# NeuroStimDuino_v1_1.net
KiCad netlist of a schematic drawn in EAGLE
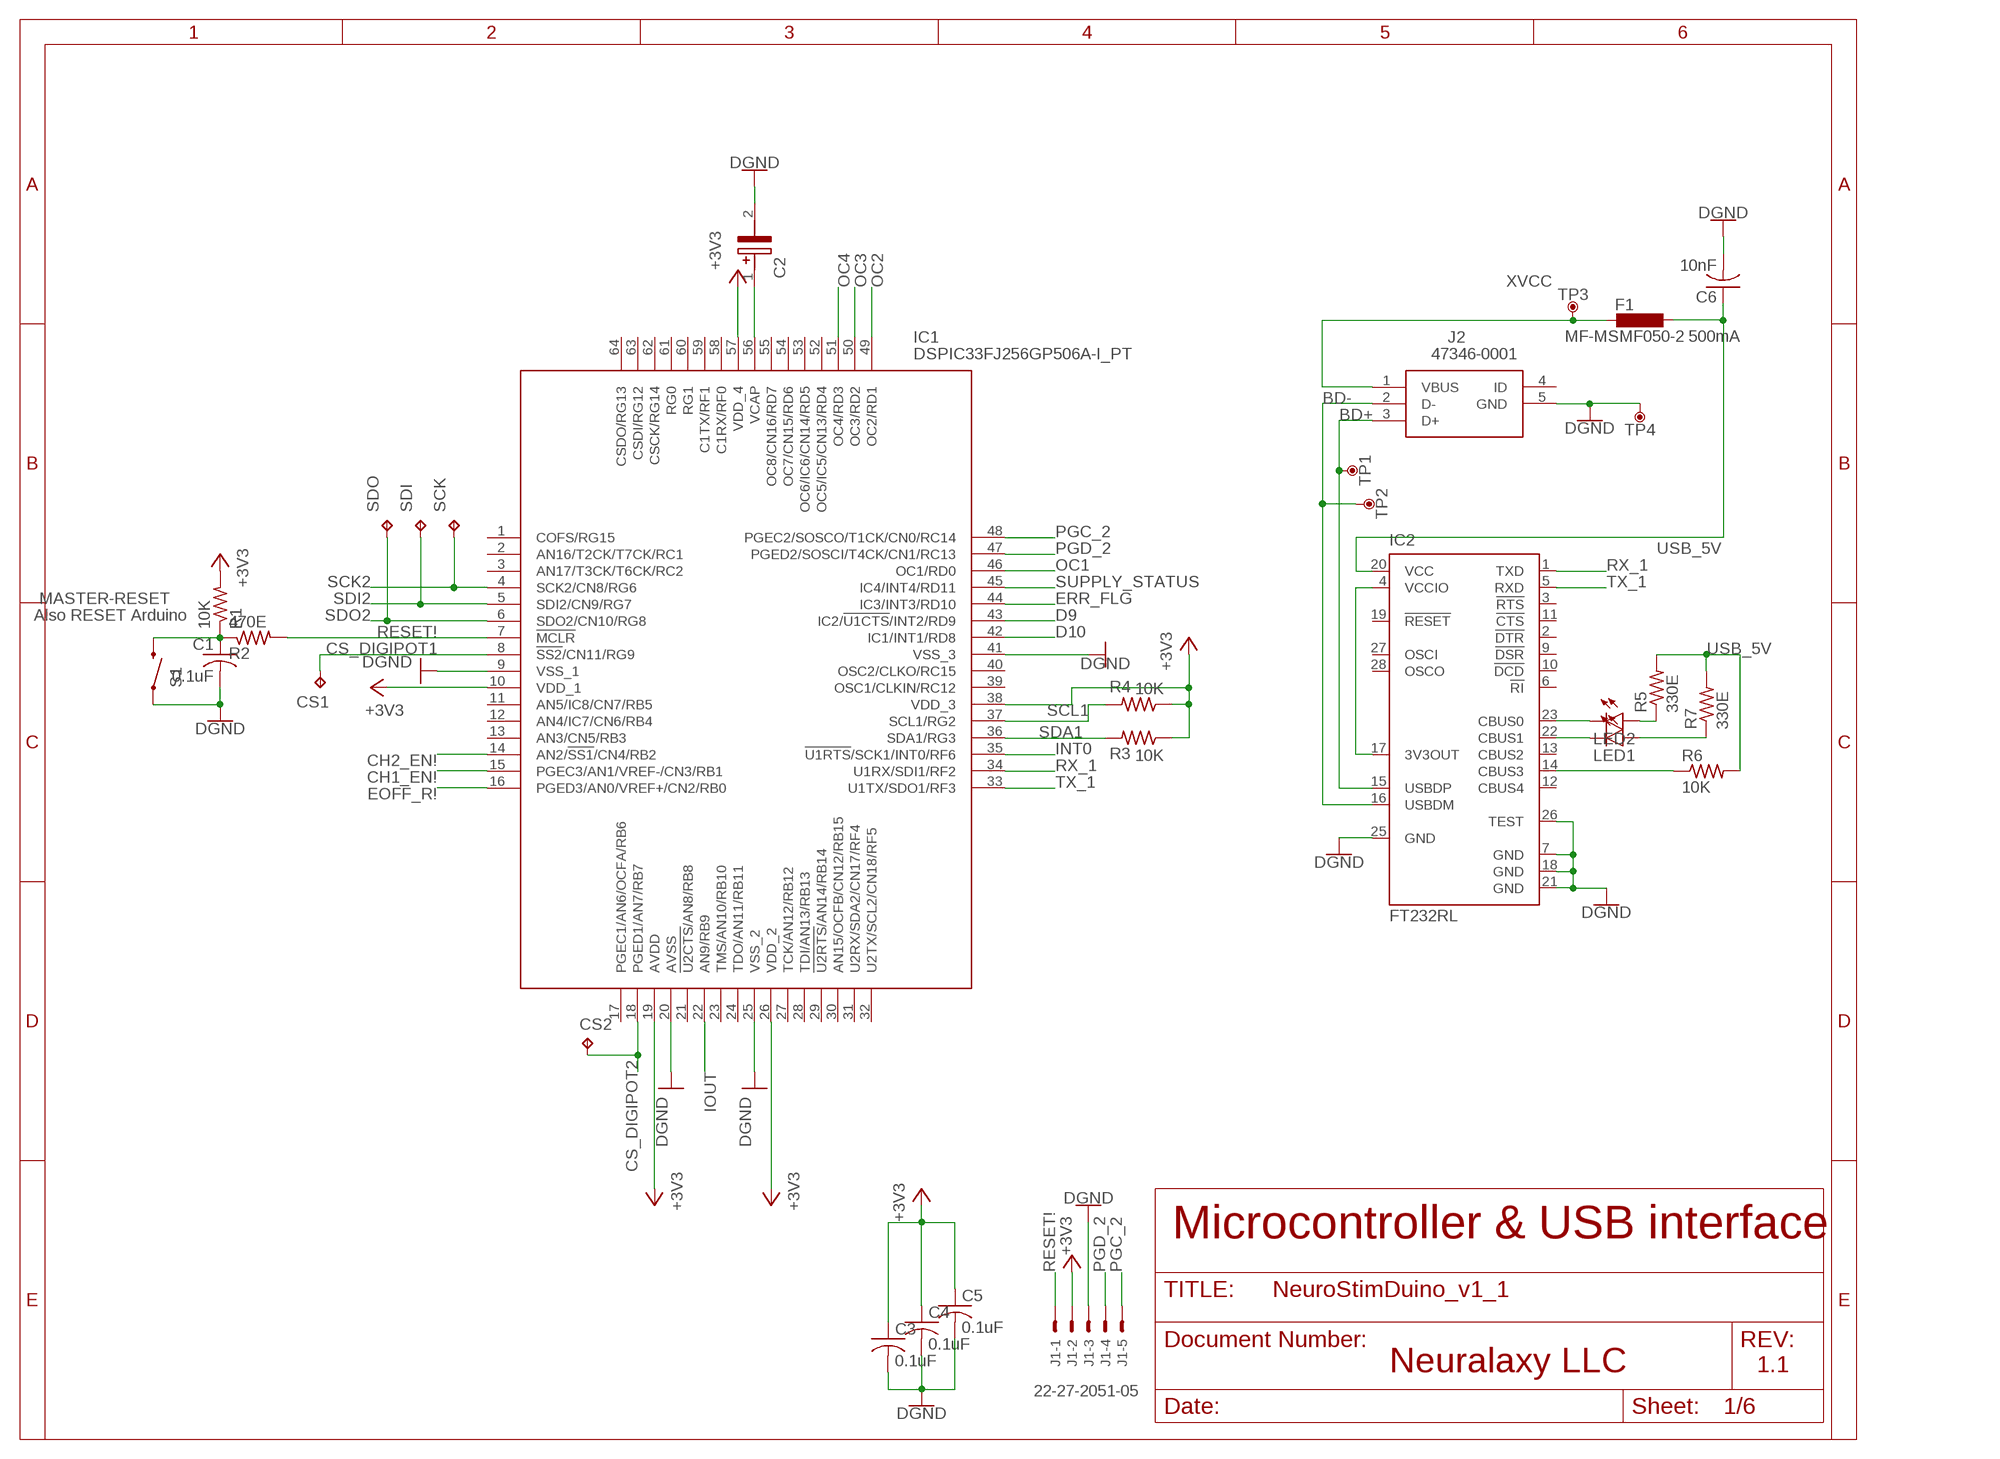
[diagram p0: schematic, sheet 1]
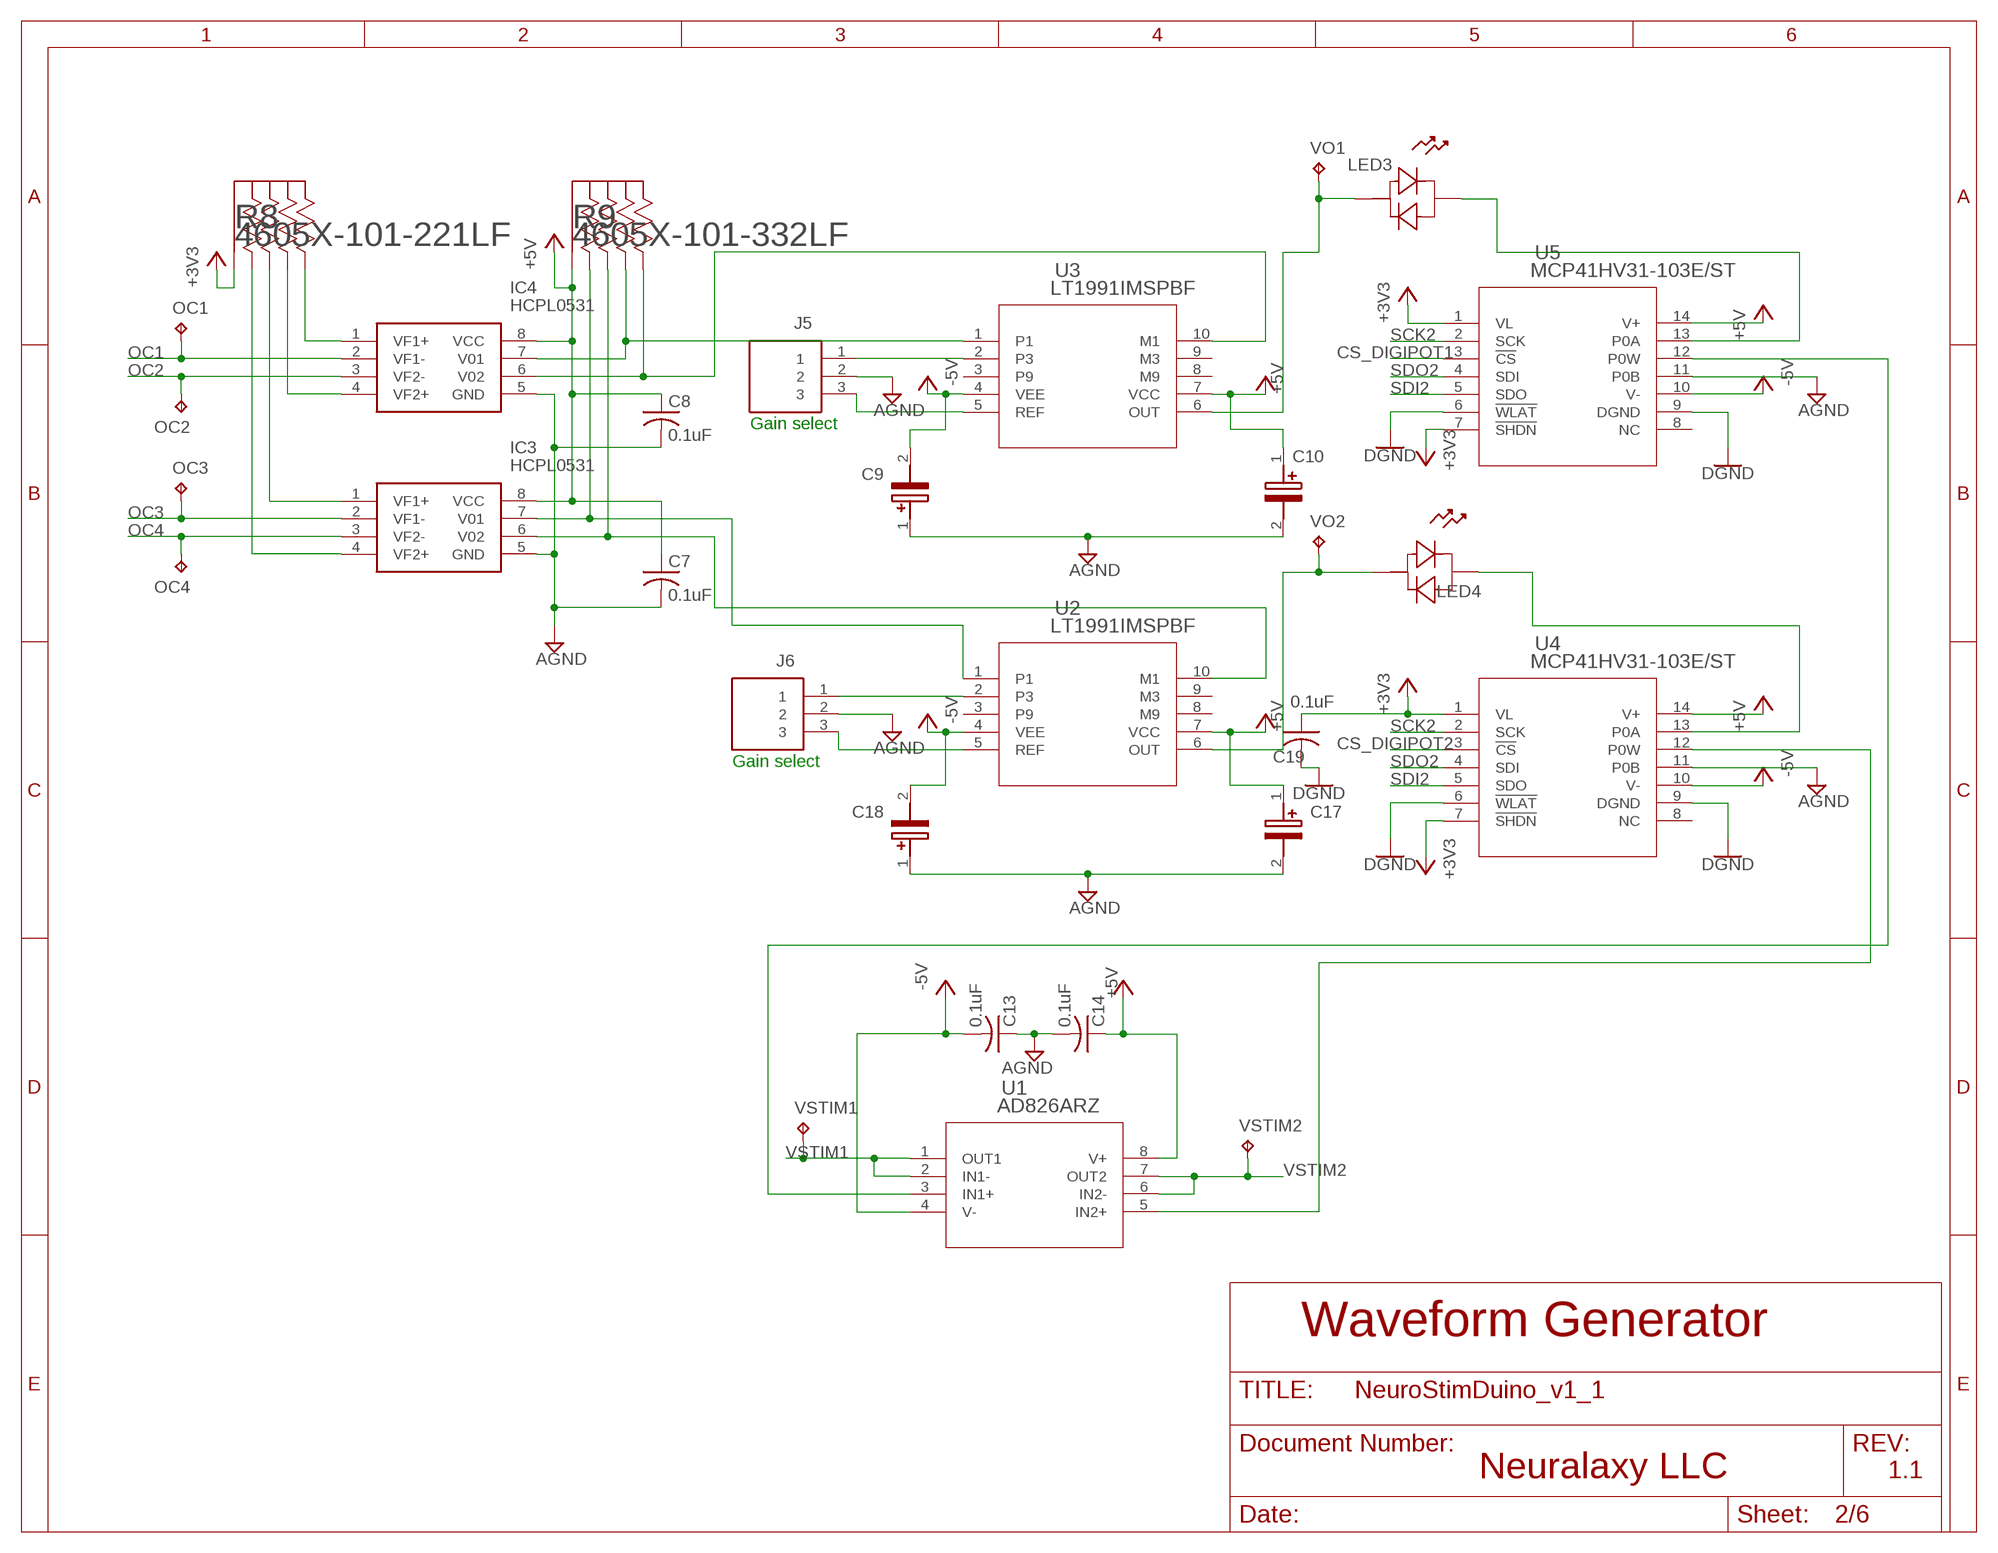
[diagram p1: schematic, sheet 2]
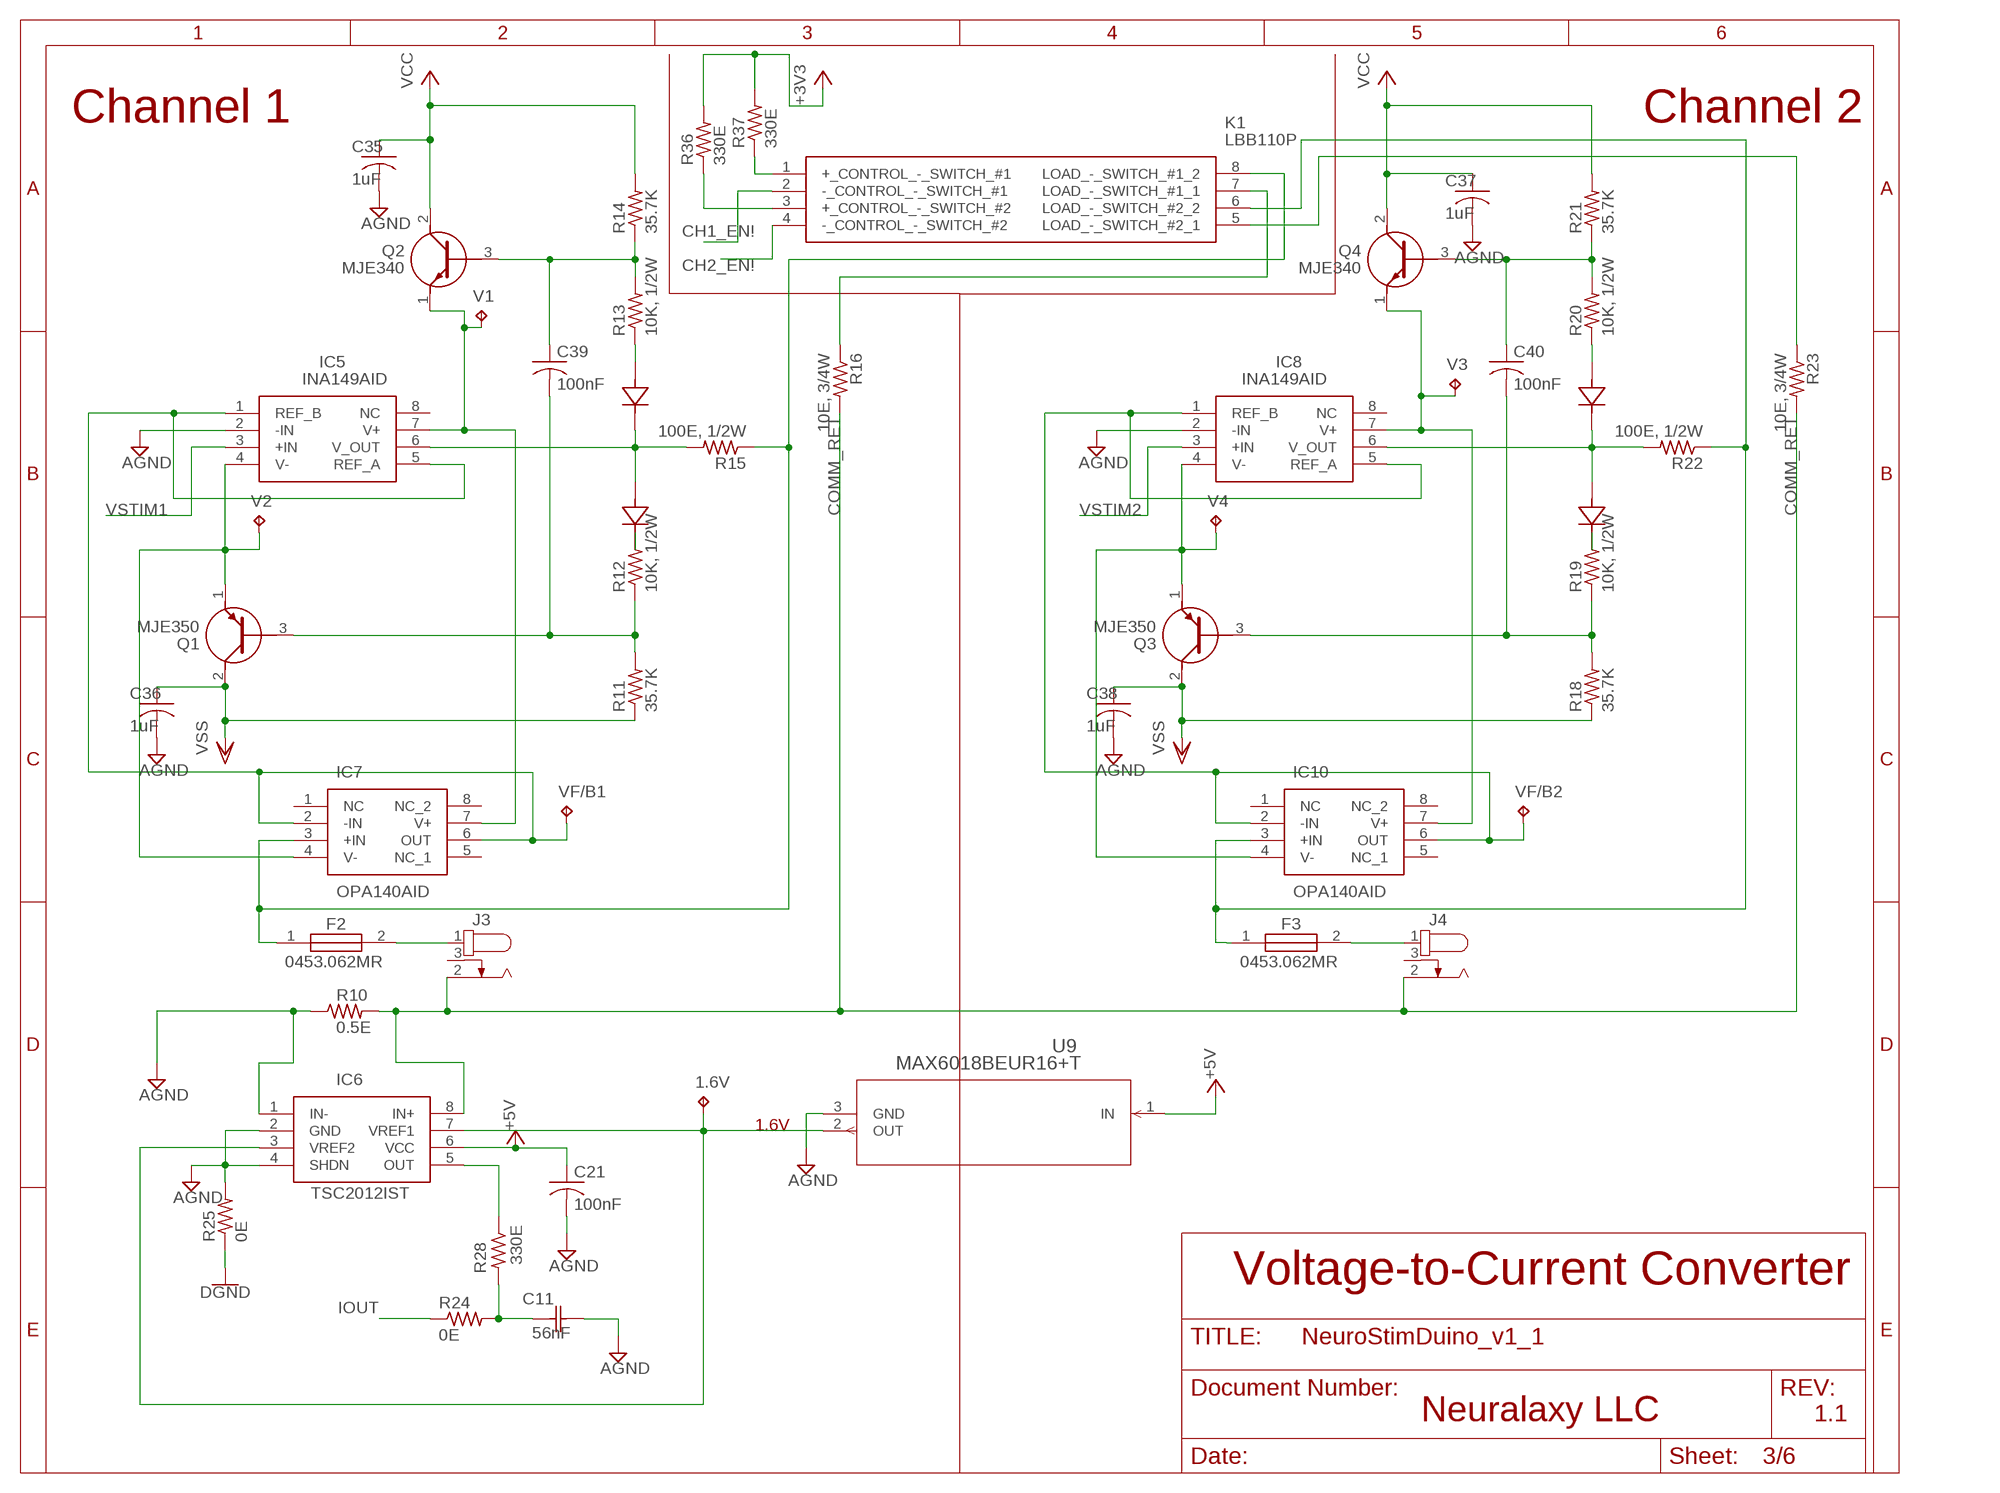
[diagram p2: schematic, sheet 3]
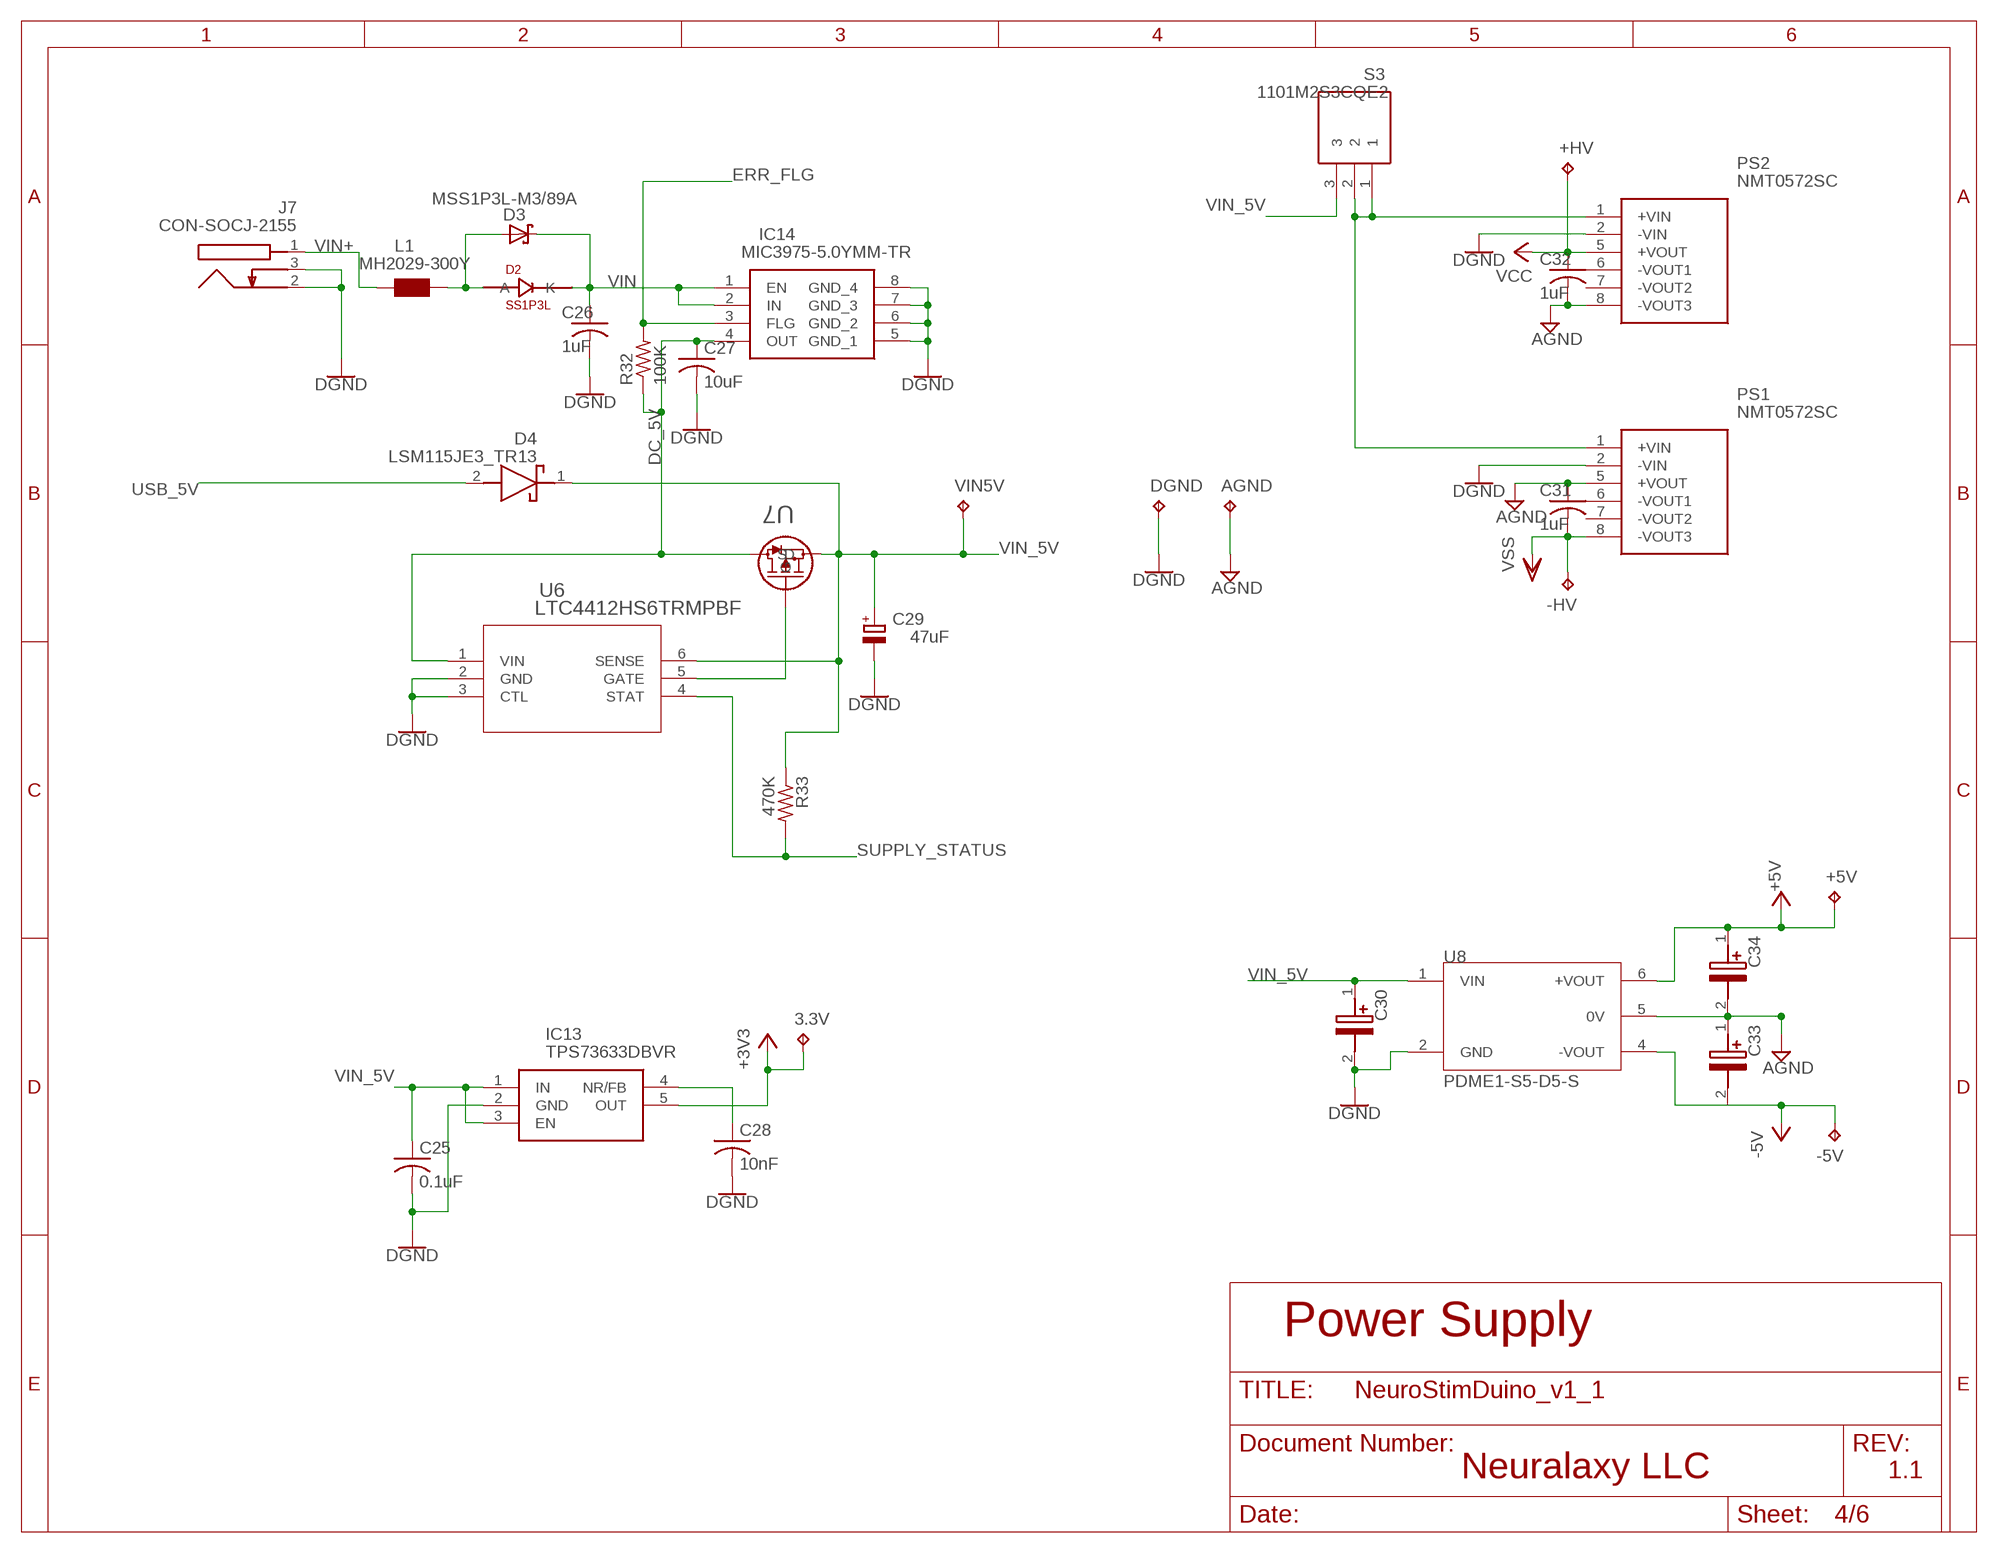
[diagram p3: schematic, sheet 4]
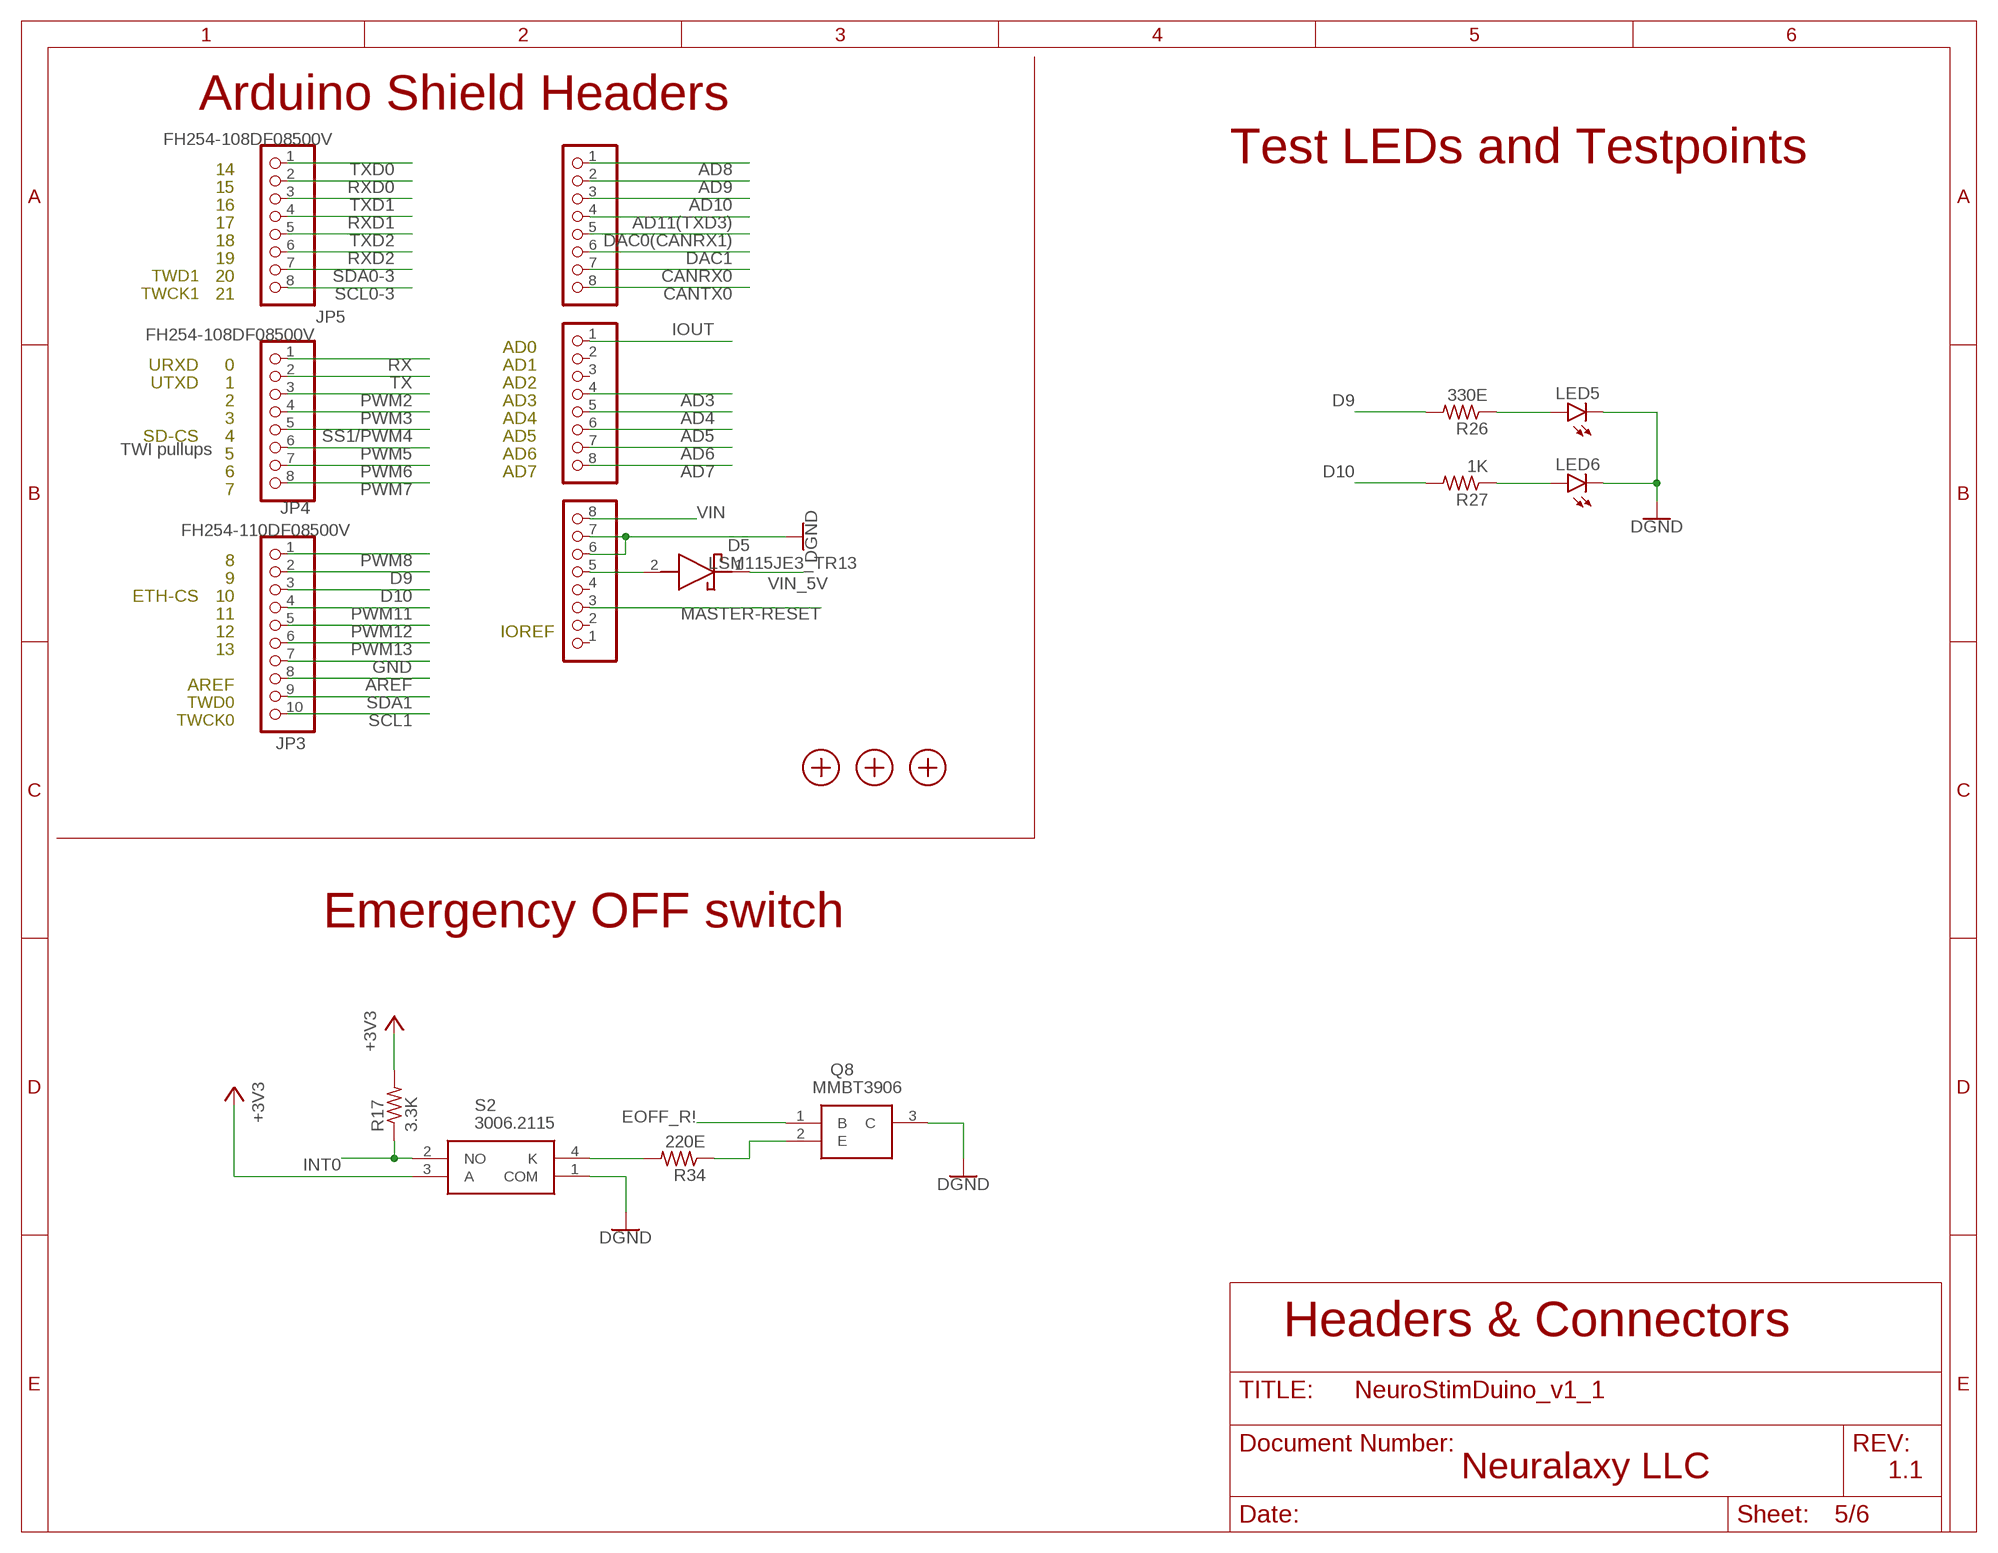
[diagram p4: schematic, sheet 5]
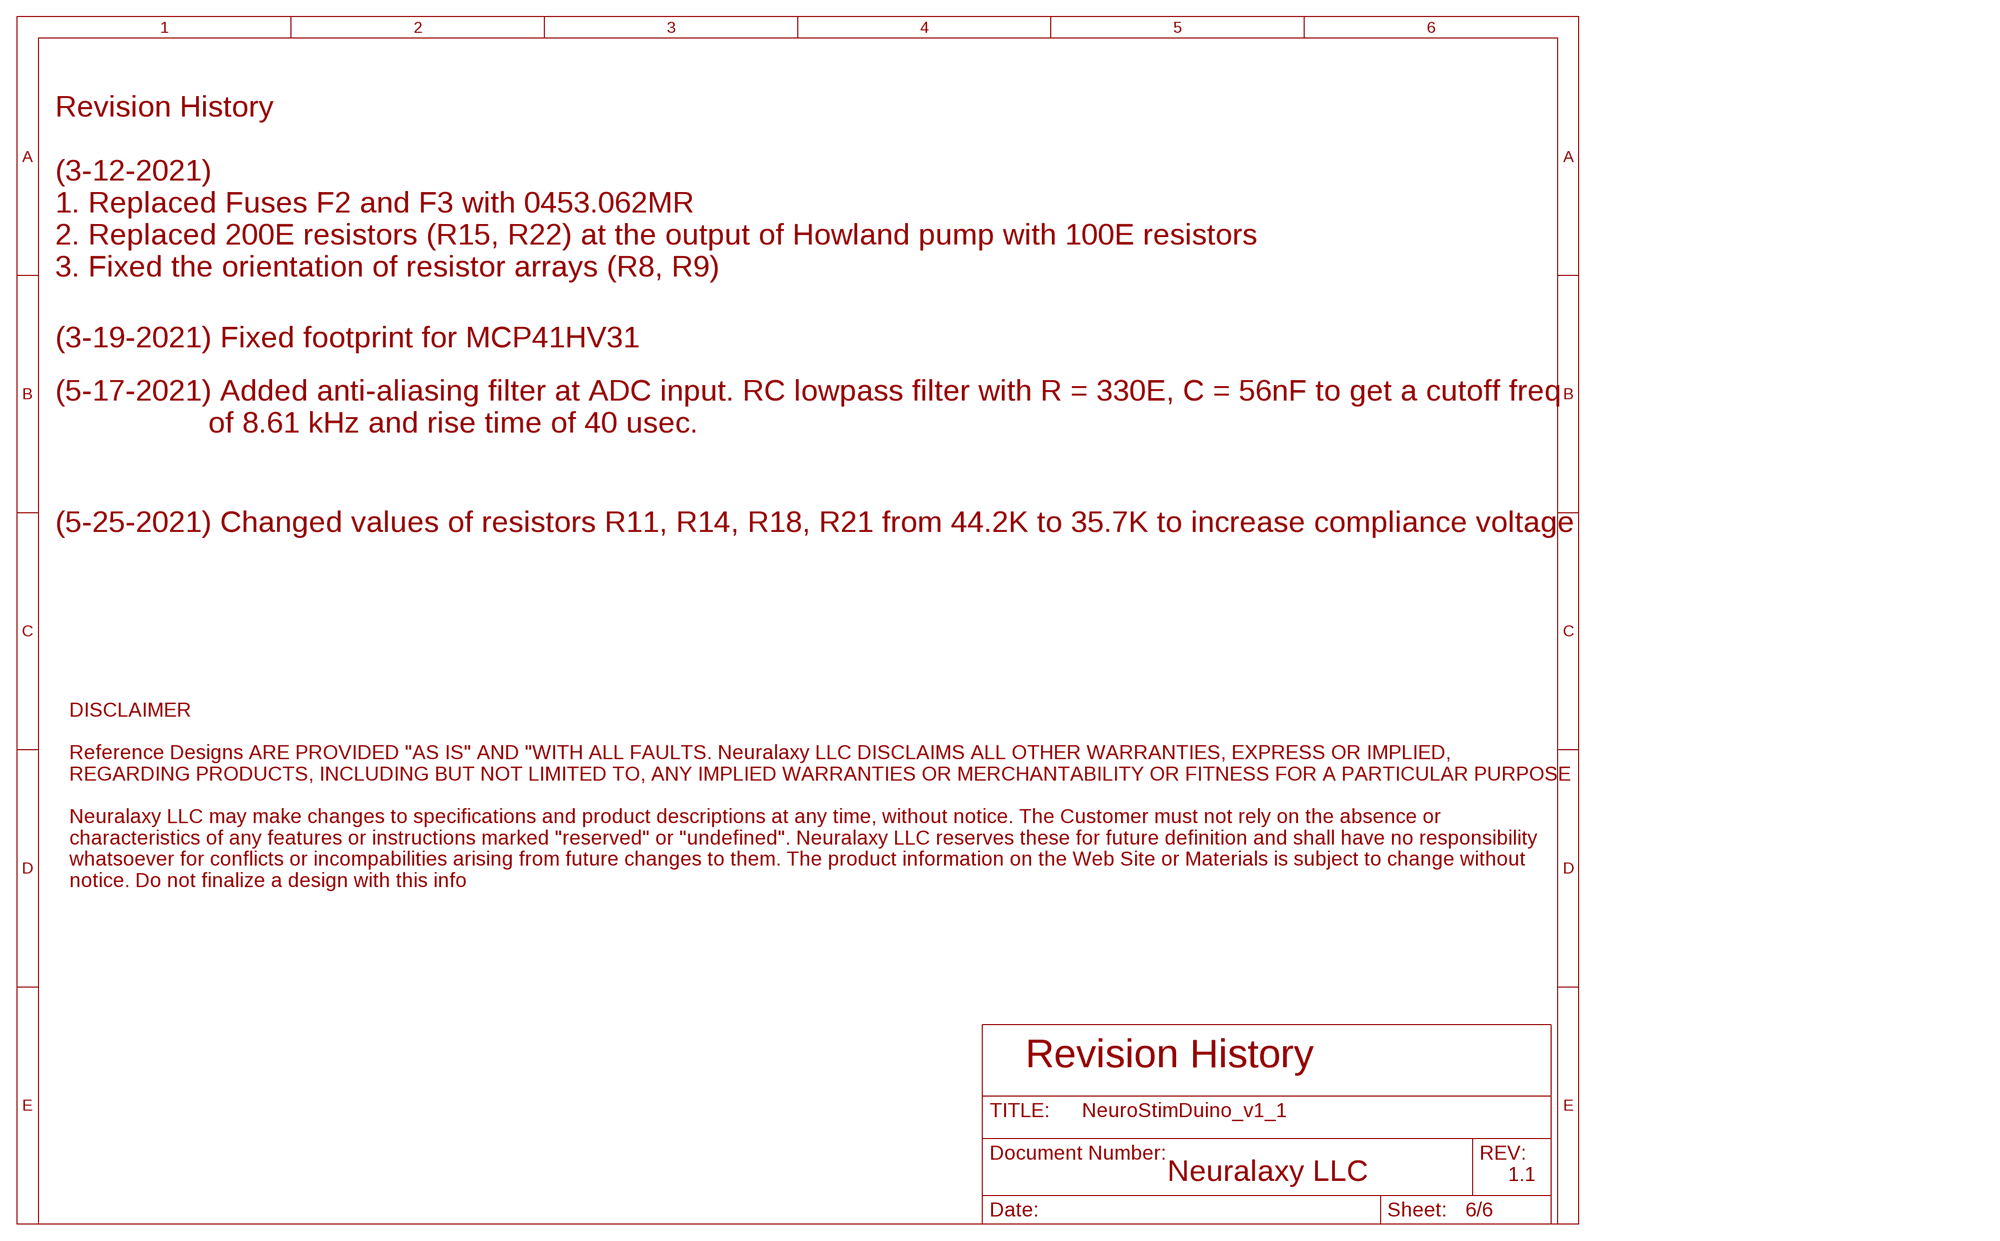
[diagram p5: schematic, sheet 6]

(export (version "E")
  (design (tool "Eeschema 10.0.6"))
  (components
    (comp (ref "1.6V")
      (value "TPTP10R")
      (footprint "eagle-import:TP10R")
      (libsource (lib "eagle-import") (part "TPTP10R"))
    )
    (comp (ref "C11")
      (value "56nF")
      (footprint "eagle-import:CAPC17595_87N_KEM")
      (fields (field (name "MANUFACTURER_PART_NUMBER") "C0603C563J4RACTU"))
      (libsource (lib "eagle-import") (part "C0603C563J4RACTU"))
    )
    (comp (ref "C21")
      (value "100nF")
      (footprint "eagle-import:C1206")
      (libsource (lib "eagle-import") (part "rcl_334_C-USC1206"))
    )
    (comp (ref "C35")
      (value "1uF")
      (footprint "eagle-import:C0805")
      (libsource (lib "eagle-import") (part "rcl_334_C-USC0805"))
    )
    (comp (ref "C36")
      (value "1uF")
      (footprint "eagle-import:C0805")
      (libsource (lib "eagle-import") (part "rcl_334_C-USC0805"))
    )
    (comp (ref "C37")
      (value "1uF")
      (footprint "eagle-import:C0805")
      (libsource (lib "eagle-import") (part "rcl_334_C-USC0805"))
    )
    (comp (ref "C38")
      (value "1uF")
      (footprint "eagle-import:C0805")
      (libsource (lib "eagle-import") (part "rcl_334_C-USC0805"))
    )
    (comp (ref "C39")
      (value "100nF")
      (footprint "eagle-import:C0805K")
      (libsource (lib "eagle-import") (part "rcl_334_C-USC0805K"))
    )
    (comp (ref "C40")
      (value "100nF")
      (footprint "eagle-import:C0805K")
      (libsource (lib "eagle-import") (part "rcl_334_C-USC0805K"))
    )
    (comp (ref "D6")
      (value "GF1J-E3DO-214BA-L")
      (footprint "eagle-import:DO-214BA-L")
      (fields (field (name "MANUFACTURER_PART_NUMBER") "GF1J-E3"))
      (libsource (lib "eagle-import") (part "GF1J-E3DO-214BA-L"))
    )
    (comp (ref "D7")
      (value "GF1J-E3DO-214BA-L")
      (footprint "eagle-import:DO-214BA-L")
      (fields (field (name "MANUFACTURER_PART_NUMBER") "GF1J-E3"))
      (libsource (lib "eagle-import") (part "GF1J-E3DO-214BA-L"))
    )
    (comp (ref "D8")
      (value "GF1J-E3DO-214BA-L")
      (footprint "eagle-import:DO-214BA-L")
      (fields (field (name "MANUFACTURER_PART_NUMBER") "GF1J-E3"))
      (libsource (lib "eagle-import") (part "GF1J-E3DO-214BA-L"))
    )
    (comp (ref "D9")
      (value "GF1J-E3DO-214BA-L")
      (footprint "eagle-import:DO-214BA-L")
      (fields (field (name "MANUFACTURER_PART_NUMBER") "GF1J-E3"))
      (libsource (lib "eagle-import") (part "GF1J-E3DO-214BA-L"))
    )
    (comp (ref "F2")
      (value "0453.062MR")
      (footprint "eagle-import:FUSC6127X294N")
      (libsource (lib "eagle-import") (part "0453.062MR"))
    )
    (comp (ref "F3")
      (value "0453.062MR")
      (footprint "eagle-import:FUSC6127X294N")
      (libsource (lib "eagle-import") (part "0453.062MR"))
    )
    (comp (ref "IC5")
      (value "INA149AID")
      (footprint "eagle-import:SOIC127P600X175-8N")
      (fields (field (name "MOUSER_PART_NUMBER") "595-INA149AID"))
      (libsource (lib "eagle-import") (part "INA149AID"))
    )
    (comp (ref "IC6")
      (value "TSC2012IST")
      (footprint "eagle-import:SOP65P490X110-8N")
      (fields
        (field (name "MANUFACTURER_PART_NUMBER") "TSC2011IST")
        (field (name "MOUSER_PART_NUMBER") "511-TSC2011IST")
      )
      (libsource (lib "eagle-import") (part "TSC2012IST"))
    )
    (comp (ref "IC7")
      (value "OPA140AID")
      (footprint "eagle-import:SOIC127P600X175-8N")
      (fields (field (name "MOUSER_PART_NUMBER") "595-OPA140AID"))
      (libsource (lib "eagle-import") (part "OPA140AID"))
    )
    (comp (ref "IC8")
      (value "INA149AID")
      (footprint "eagle-import:SOIC127P600X175-8N")
      (fields (field (name "MOUSER_PART_NUMBER") "595-INA149AID"))
      (libsource (lib "eagle-import") (part "INA149AID"))
    )
    (comp (ref "IC10")
      (value "OPA140AID")
      (footprint "eagle-import:SOIC127P600X175-8N")
      (fields (field (name "MOUSER_PART_NUMBER") "595-OPA140AID"))
      (libsource (lib "eagle-import") (part "OPA140AID"))
    )
    (comp (ref "J3")
      (value "694101308002")
      (footprint "eagle-import:694101308002")
      (libsource (lib "eagle-import") (part "694101308002"))
    )
    (comp (ref "J4")
      (value "694101308002")
      (footprint "eagle-import:694101308002")
      (libsource (lib "eagle-import") (part "694101308002"))
    )
    (comp (ref "K1")
      (value "LBB110P")
      (footprint "eagle-import:SOP254P940X229-8N")
      (fields (field (name "MOUSER_PART_NUMBER") "849-LBB110P"))
      (libsource (lib "eagle-import") (part "LBB110P"))
    )
    (comp (ref "Q1")
      (value "MJE350")
      (footprint "eagle-import:TO229P300X760X1364-3P")
      (fields
        (field (name "MANUFACTURER_PART_NUMBER") "MJE350G")
        (field (name "MOUSER_PART_NUMBER") "863-MJE350G")
      )
      (libsource (lib "eagle-import") (part "MJE350"))
    )
    (comp (ref "Q2")
      (value "MJE340")
      (footprint "eagle-import:TO229P290X760X1320-3P")
      (fields (field (name "MOUSER_PART_NUMBER") "511-MJE340"))
      (libsource (lib "eagle-import") (part "MJE340"))
    )
    (comp (ref "Q3")
      (value "MJE350")
      (footprint "eagle-import:TO229P300X760X1364-3P")
      (fields
        (field (name "MANUFACTURER_PART_NUMBER") "MJE350G")
        (field (name "MOUSER_PART_NUMBER") "863-MJE350G")
      )
      (libsource (lib "eagle-import") (part "MJE350"))
    )
    (comp (ref "Q4")
      (value "MJE340")
      (footprint "eagle-import:TO229P290X760X1320-3P")
      (fields (field (name "MOUSER_PART_NUMBER") "511-MJE340"))
      (libsource (lib "eagle-import") (part "MJE340"))
    )
    (comp (ref "R10")
      (value "0.5E")
      (footprint "eagle-import:R1206")
      (libsource (lib "eagle-import") (part "rcl_334_R-US_R1206"))
    )
    (comp (ref "R11")
      (value "35.7K")
      (footprint "eagle-import:R1206")
      (libsource (lib "eagle-import") (part "rcl_334_R-US_R1206"))
    )
    (comp (ref "R12")
      (value "10K, 1/2W")
      (footprint "eagle-import:R1206")
      (libsource (lib "eagle-import") (part "rcl_334_R-US_R1206"))
    )
    (comp (ref "R13")
      (value "10K, 1/2W")
      (footprint "eagle-import:R1206")
      (libsource (lib "eagle-import") (part "rcl_334_R-US_R1206"))
    )
    (comp (ref "R14")
      (value "35.7K")
      (footprint "eagle-import:R1206")
      (libsource (lib "eagle-import") (part "rcl_334_R-US_R1206"))
    )
    (comp (ref "R15")
      (value "100E, 1/2W")
      (footprint "eagle-import:R1206")
      (libsource (lib "eagle-import") (part "rcl_334_R-US_R1206"))
    )
    (comp (ref "R16")
      (value "10E, 3/4W")
      (footprint "eagle-import:R1206")
      (libsource (lib "eagle-import") (part "rcl_334_R-US_R1206"))
    )
    (comp (ref "R18")
      (value "35.7K")
      (footprint "eagle-import:R1206")
      (libsource (lib "eagle-import") (part "rcl_334_R-US_R1206"))
    )
    (comp (ref "R19")
      (value "10K, 1/2W")
      (footprint "eagle-import:R1206")
      (libsource (lib "eagle-import") (part "rcl_334_R-US_R1206"))
    )
    (comp (ref "R20")
      (value "10K, 1/2W")
      (footprint "eagle-import:R1206")
      (libsource (lib "eagle-import") (part "rcl_334_R-US_R1206"))
    )
    (comp (ref "R21")
      (value "35.7K")
      (footprint "eagle-import:R1206")
      (libsource (lib "eagle-import") (part "rcl_334_R-US_R1206"))
    )
    (comp (ref "R22")
      (value "100E, 1/2W")
      (footprint "eagle-import:R1206")
      (libsource (lib "eagle-import") (part "rcl_334_R-US_R1206"))
    )
    (comp (ref "R23")
      (value "10E, 3/4W")
      (footprint "eagle-import:R1206")
      (libsource (lib "eagle-import") (part "rcl_334_R-US_R1206"))
    )
    (comp (ref "R24")
      (value "0E")
      (footprint "eagle-import:R1206")
      (libsource (lib "eagle-import") (part "rcl_334_R-US_R1206"))
    )
    (comp (ref "R25")
      (value "0E")
      (footprint "eagle-import:R1206")
      (libsource (lib "eagle-import") (part "rcl_334_R-US_R1206"))
    )
    (comp (ref "R28")
      (value "330E")
      (footprint "eagle-import:R0603")
      (libsource (lib "eagle-import") (part "R-US_R0603"))
    )
    (comp (ref "R36")
      (value "330E")
      (footprint "eagle-import:R1206")
      (libsource (lib "eagle-import") (part "R-US_R1206"))
    )
    (comp (ref "R37")
      (value "330E")
      (footprint "eagle-import:R1206")
      (libsource (lib "eagle-import") (part "R-US_R1206"))
    )
    (comp (ref "U9")
      (value "MAX6018BEUR16+T")
      (footprint "eagle-import:21-0051H_MXM")
      (libsource (lib "eagle-import") (part "MAX6018BEUR16+T"))
    )
    (comp (ref "V1")
      (value "TPTP10R")
      (footprint "eagle-import:TP10R")
      (libsource (lib "eagle-import") (part "TPTP10R"))
    )
    (comp (ref "V2")
      (value "TPTP10R")
      (footprint "eagle-import:TP10R")
      (libsource (lib "eagle-import") (part "TPTP10R"))
    )
    (comp (ref "V3")
      (value "TPTP10R")
      (footprint "eagle-import:TP10R")
      (libsource (lib "eagle-import") (part "TPTP10R"))
    )
    (comp (ref "V4")
      (value "TPTP10R")
      (footprint "eagle-import:TP10R")
      (libsource (lib "eagle-import") (part "TPTP10R"))
    )
    (comp (ref "VF/B1")
      (value "TPTP10R")
      (footprint "eagle-import:TP10R")
      (libsource (lib "eagle-import") (part "TPTP10R"))
    )
    (comp (ref "VF/B2")
      (value "TPTP10R")
      (footprint "eagle-import:TP10R")
      (libsource (lib "eagle-import") (part "TPTP10R"))
    )
    (comp (ref "C1")
      (value "0.1uF")
      (footprint "eagle-import:C1206")
      (libsource (lib "eagle-import") (part "C-USC1206"))
    )
    (comp (ref "C2")
      (value "F971C475MAAHT3")
      (footprint "eagle-import:CAPPM3216X180N")
      (fields (field (name "MOUSER_PART_NUMBER") "581-F971C475MAAHT3"))
      (libsource (lib "eagle-import") (part "F971C475MAAHT3"))
    )
    (comp (ref "C3")
      (value "0.1uF")
      (footprint "eagle-import:C1206")
      (libsource (lib "eagle-import") (part "C-USC1206"))
    )
    (comp (ref "C4")
      (value "0.1uF")
      (footprint "eagle-import:C1206")
      (libsource (lib "eagle-import") (part "C-USC1206"))
    )
    (comp (ref "C5")
      (value "0.1uF")
      (footprint "eagle-import:C1206")
      (libsource (lib "eagle-import") (part "C-USC1206"))
    )
    (comp (ref "C6")
      (value "10nF")
      (footprint "eagle-import:C1206")
      (libsource (lib "eagle-import") (part "rcl_334_C-USC1206"))
    )
    (comp (ref "CS1")
      (value "TPTP08R")
      (footprint "eagle-import:TP08R")
      (libsource (lib "eagle-import") (part "TPTP08R"))
    )
    (comp (ref "CS2")
      (value "TPTP08R")
      (footprint "eagle-import:TP08R")
      (libsource (lib "eagle-import") (part "TPTP08R"))
    )
    (comp (ref "F1")
      (value "MF-MSMF050-2 500mA")
      (footprint "eagle-import:L1812")
      (fields (field (name "PART_NUMBER") "MF-MSMF050-2"))
      (libsource (lib "eagle-import") (part "0002_MF-MSMF050-2"))
    )
    (comp (ref "IC1")
      (value "DSPIC33FJ256GP506A-I_PT")
      (footprint "eagle-import:QFP50P1200X1200X120-64N")
      (fields
        (field (name "MANUFACTURER_PART_NUMBER") "dsPIC33FJ256GP506A-I/PT")
        (field (name "MOUSER_PART_NUMBER") "579-FJ256GP506A-I/PT")
      )
      (libsource (lib "eagle-import") (part "DSPIC33FJ256GP506A-I_PT"))
    )
    (comp (ref "IC2")
      (value "FT232RL")
      (footprint "eagle-import:SSOP28")
      (libsource (lib "eagle-import") (part "FT232RL"))
    )
    (comp (ref "J1")
      (value "22-27-2051-05")
      (footprint "eagle-import:6410-05")
      (fields (field (name "MF") "MOLEX"))
      (libsource (lib "eagle-import") (part "22-?-0527-2051"))
    )
    (comp (ref "J2")
      (value "47346-0001")
      (footprint "eagle-import:47346-0001")
      (fields (field (name "MOUSER_PART_NUMBER") "538-47346-0001"))
      (libsource (lib "eagle-import") (part "47346-0001"))
    )
    (comp (ref "LED1")
      (value "LEDCHIPLED_1206")
      (footprint "eagle-import:CHIPLED_1206")
      (libsource (lib "eagle-import") (part "LEDCHIPLED_1206"))
    )
    (comp (ref "LED2")
      (value "LEDCHIPLED_1206")
      (footprint "eagle-import:CHIPLED_1206")
      (libsource (lib "eagle-import") (part "LEDCHIPLED_1206"))
    )
    (comp (ref "R1")
      (value "10K")
      (footprint "eagle-import:R1206")
      (libsource (lib "eagle-import") (part "R-US_R1206"))
    )
    (comp (ref "R2")
      (value "470E")
      (footprint "eagle-import:R1206")
      (libsource (lib "eagle-import") (part "R-US_R1206"))
    )
    (comp (ref "R3")
      (value "10K")
      (footprint "eagle-import:R1206")
      (libsource (lib "eagle-import") (part "R-US_R1206"))
    )
    (comp (ref "R4")
      (value "10K")
      (footprint "eagle-import:R1206")
      (libsource (lib "eagle-import") (part "R-US_R1206"))
    )
    (comp (ref "R5")
      (value "330E")
      (footprint "eagle-import:R1206")
      (libsource (lib "eagle-import") (part "R-US_R1206"))
    )
    (comp (ref "R6")
      (value "10K")
      (footprint "eagle-import:R1206")
      (libsource (lib "eagle-import") (part "R-US_R1206"))
    )
    (comp (ref "R7")
      (value "330E")
      (footprint "eagle-import:R1206")
      (libsource (lib "eagle-import") (part "R-US_R1206"))
    )
    (comp (ref "S1")
      (value "SWITCH-MOMENTARY-2SMD")
      (footprint "eagle-import:TACTILE_SWITCH_SMD")
      (libsource (lib "eagle-import") (part "SWITCH-MOMENTARY-2SMD"))
    )
    (comp (ref "SCK")
      (value "TPTP10R")
      (footprint "eagle-import:TP10R")
      (libsource (lib "eagle-import") (part "TPTP10R"))
    )
    (comp (ref "SDI")
      (value "TPTP10R")
      (footprint "eagle-import:TP10R")
      (libsource (lib "eagle-import") (part "TPTP10R"))
    )
    (comp (ref "SDO")
      (value "TPTP10R")
      (footprint "eagle-import:TP10R")
      (libsource (lib "eagle-import") (part "TPTP10R"))
    )
    (comp (ref "TP1")
      (value "DNP")
      (footprint "eagle-import:TP-1.00MM")
      (libsource (lib "eagle-import") (part "TPTP-1.00MM"))
    )
    (comp (ref "TP2")
      (value "DNP")
      (footprint "eagle-import:TP-1.00MM")
      (libsource (lib "eagle-import") (part "TPTP-1.00MM"))
    )
    (comp (ref "TP3")
      (value "DNP")
      (footprint "eagle-import:TP-1.00MM")
      (libsource (lib "eagle-import") (part "TPTP-1.00MM"))
    )
    (comp (ref "TP4")
      (value "DNP")
      (footprint "eagle-import:TP-1.00MM")
      (libsource (lib "eagle-import") (part "TPTP-1.00MM"))
    )
    (comp (ref "C7")
      (value "0.1uF")
      (footprint "eagle-import:C1206")
      (libsource (lib "eagle-import") (part "rcl_334_C-USC1206"))
    )
    (comp (ref "C8")
      (value "0.1uF")
      (footprint "eagle-import:C1206")
      (libsource (lib "eagle-import") (part "rcl_334_C-USC1206"))
    )
    (comp (ref "C9")
      (value "F971C475MAAHT3")
      (footprint "eagle-import:CAPPM3216X180N")
      (fields (field (name "MOUSER_PART_NUMBER") "581-F971C475MAAHT3"))
      (libsource (lib "eagle-import") (part "F971C475MAAHT3"))
    )
    (comp (ref "C10")
      (value "F971C475MAAHT3")
      (footprint "eagle-import:CAPPM3216X180N")
      (fields (field (name "MOUSER_PART_NUMBER") "581-F971C475MAAHT3"))
      (libsource (lib "eagle-import") (part "F971C475MAAHT3"))
    )
    (comp (ref "C13")
      (value "0.1uF")
      (footprint "eagle-import:C1206")
      (libsource (lib "eagle-import") (part "rcl_334_C-USC1206"))
    )
    (comp (ref "C14")
      (value "0.1uF")
      (footprint "eagle-import:C1206")
      (libsource (lib "eagle-import") (part "rcl_334_C-USC1206"))
    )
    (comp (ref "C17")
      (value "F971C475MAAHT3")
      (footprint "eagle-import:CAPPM3216X180N")
      (fields (field (name "MOUSER_PART_NUMBER") "581-F971C475MAAHT3"))
      (libsource (lib "eagle-import") (part "F971C475MAAHT3"))
    )
    (comp (ref "C18")
      (value "F971C475MAAHT3")
      (footprint "eagle-import:CAPPM3216X180N")
      (fields (field (name "MOUSER_PART_NUMBER") "581-F971C475MAAHT3"))
      (libsource (lib "eagle-import") (part "F971C475MAAHT3"))
    )
    (comp (ref "C19")
      (value "0.1uF")
      (footprint "eagle-import:C1206")
      (libsource (lib "eagle-import") (part "rcl_334_C-USC1206"))
    )
    (comp (ref "IC3")
      (value "HCPL0531")
      (footprint "eagle-import:SOIC127P594X363-8N")
      (fields (field (name "MOUSER_PART_NUMBER") "512-HCPL0531"))
      (libsource (lib "eagle-import") (part "HCPL0531"))
    )
    (comp (ref "IC4")
      (value "HCPL0531")
      (footprint "eagle-import:SOIC127P594X363-8N")
      (fields (field (name "MOUSER_PART_NUMBER") "512-HCPL0531"))
      (libsource (lib "eagle-import") (part "HCPL0531"))
    )
    (comp (ref "J5")
      (value "TMS-103-02-L-S")
      (footprint "eagle-import:TMS-103-YY-XX-S")
      (fields (field (name "MOUSER_PART_NUMBER") "200-TMS10302LS"))
      (libsource (lib "eagle-import") (part "TMS-103-02-L-S"))
    )
    (comp (ref "J6")
      (value "TMS-103-02-L-S")
      (footprint "eagle-import:TMS-103-YY-XX-S")
      (fields (field (name "MOUSER_PART_NUMBER") "200-TMS10302LS"))
      (libsource (lib "eagle-import") (part "TMS-103-02-L-S"))
    )
    (comp (ref "LED3")
      (value "XZMDKVG55W-4")
      (footprint "eagle-import:LED_KVG55W-4_SLD")
      (fields (field (name "COPYRIGHT") "Copyright (C) 2018 Accelerated Designs. All rights reserved"))
      (libsource (lib "eagle-import") (part "XZMDKVG55W-4"))
    )
    (comp (ref "LED4")
      (value "XZMDKVG55W-4")
      (footprint "eagle-import:LED_KVG55W-4_SLD")
      (fields (field (name "COPYRIGHT") "Copyright (C) 2018 Accelerated Designs. All rights reserved"))
      (libsource (lib "eagle-import") (part "XZMDKVG55W-4"))
    )
    (comp (ref "OC1")
      (value "TPTP08R")
      (footprint "eagle-import:TP08R")
      (libsource (lib "eagle-import") (part "TPTP08R"))
    )
    (comp (ref "OC2")
      (value "TPTP08R")
      (footprint "eagle-import:TP08R")
      (libsource (lib "eagle-import") (part "TPTP08R"))
    )
    (comp (ref "OC3")
      (value "TPTP10R")
      (footprint "eagle-import:TP10R")
      (libsource (lib "eagle-import") (part "TPTP10R"))
    )
    (comp (ref "OC4")
      (value "TPTP10R")
      (footprint "eagle-import:TP10R")
      (libsource (lib "eagle-import") (part "TPTP10R"))
    )
    (comp (ref "R8")
      (value "4605X-101-221LF")
      (footprint "eagle-import:BO_4605X")
      (fields (field (name "MANUFACTURER_PART_NUMBER") "4605X-101-222LF"))
      (libsource (lib "eagle-import") (part "4605X-101-221LF"))
    )
    (comp (ref "R9")
      (value "4605X-101-332LF")
      (footprint "eagle-import:BO_4605X")
      (fields (field (name "MANUFACTURER_PART_NUMBER") "4605X-101-222LF"))
      (libsource (lib "eagle-import") (part "4605X-101-332LF"))
    )
    (comp (ref "U1")
      (value "AD826ARZ")
      (footprint "eagle-import:R_8_ADI")
      (libsource (lib "eagle-import") (part "AD826ARZ"))
    )
    (comp (ref "U2")
      (value "LT1991IMSPBF")
      (footprint "eagle-import:MSOP-10_MS_LIT")
      (fields (field (name "MANUFACTURER_PART_NUMBER") "LT1991IMS#PBF"))
      (libsource (lib "eagle-import") (part "LT1991IMSPBF"))
    )
    (comp (ref "U3")
      (value "LT1991IMSPBF")
      (footprint "eagle-import:MSOP-10_MS_LIT")
      (fields (field (name "MANUFACTURER_PART_NUMBER") "LT1991IMS#PBF"))
      (libsource (lib "eagle-import") (part "LT1991IMSPBF"))
    )
    (comp (ref "U4")
      (value "MCP41HV31-103E/ST")
      (footprint "eagle-import:TSSOP14_MC_MCH")
      (fields (field (name "COPYRIGHT") "Copyright (C) 2018 Accelerated Designs. All rights reserved"))
      (libsource (lib "eagle-import") (part "MCP41HV31-103E/ST"))
    )
    (comp (ref "U5")
      (value "MCP41HV31-103E/ST")
      (footprint "eagle-import:TSSOP14_MC_MCH")
      (fields (field (name "COPYRIGHT") "Copyright (C) 2018 Accelerated Designs. All rights reserved"))
      (libsource (lib "eagle-import") (part "MCP41HV31-103E/ST"))
    )
    (comp (ref "VO1")
      (value "TPTP10R")
      (footprint "eagle-import:TP10R")
      (libsource (lib "eagle-import") (part "TPTP10R"))
    )
    (comp (ref "VO2")
      (value "TPTP10R")
      (footprint "eagle-import:TP10R")
      (libsource (lib "eagle-import") (part "TPTP10R"))
    )
    (comp (ref "VSTIM1")
      (value "TPTP08R")
      (footprint "eagle-import:TP08R")
      (libsource (lib "eagle-import") (part "TPTP08R"))
    )
    (comp (ref "VSTIM2")
      (value "TPTP08R")
      (footprint "eagle-import:TP08R")
      (libsource (lib "eagle-import") (part "TPTP08R"))
    )
    (comp (ref "D5")
      (value "LSM115JE3_TR13")
      (footprint "eagle-import:DIOM5436X330N")
      (fields
        (field (name "ARROW_PART_NUMBER") "LSM115JE3/TR13")
        (field (name "MOUSER_PART_NUMBER") "494-LSM115JE3/TR13")
      )
      (libsource (lib "eagle-import") (part "LSM115JE3_TR13"))
    )
    (comp (ref "JP3")
      (value "FH254-110DF08500V")
      (footprint "eagle-import:1X10")
      (fields (field (name "PART_NUMBER") "20TW-537"))
      (libsource (lib "eagle-import") (part "1684_20TW-537"))
    )
    (comp (ref "JP4")
      (value "FH254-108DF08500V")
      (footprint "eagle-import:1X08")
      (fields (field (name "PART_NUMBER") "20TW-536"))
      (libsource (lib "eagle-import") (part "1683_20TW-536"))
    )
    (comp (ref "JP5")
      (value "FH254-108DF08500V")
      (footprint "eagle-import:1X08")
      (fields (field (name "PART_NUMBER") "20TW-536"))
      (libsource (lib "eagle-import") (part "1683_20TW-536"))
    )
    (comp (ref "JP6")
      (value "FH254-108DF08500V")
      (footprint "eagle-import:1X08")
      (fields (field (name "PART_NUMBER") "20TW-536"))
      (libsource (lib "eagle-import") (part "1683_20TW-536"))
    )
    (comp (ref "JP7")
      (value "FH254-108DF08500V")
      (footprint "eagle-import:1X08")
      (fields (field (name "PART_NUMBER") "20TW-536"))
      (libsource (lib "eagle-import") (part "1683_20TW-536"))
    )
    (comp (ref "JP8")
      (value "FH254-108DF08500V")
      (footprint "eagle-import:1X08")
      (fields (field (name "PART_NUMBER") "20TW-536"))
      (libsource (lib "eagle-import") (part "1683_20TW-536"))
    )
    (comp (ref "LED5")
      (value "LEDCHIPLED_1206")
      (footprint "eagle-import:CHIPLED_1206")
      (libsource (lib "eagle-import") (part "LEDCHIPLED_1206"))
    )
    (comp (ref "LED6")
      (value "LEDCHIPLED_1206")
      (footprint "eagle-import:CHIPLED_1206")
      (libsource (lib "eagle-import") (part "LEDCHIPLED_1206"))
    )
    (comp (ref "Q8")
      (value "MMBT3906")
      (footprint "eagle-import:SOT95P240X120-3N")
      (fields (field (name "MOUSER_PART_NUMBER") "512-MMBT3906"))
      (libsource (lib "eagle-import") (part "MMBT3906"))
    )
    (comp (ref "R17")
      (value "3.3K")
      (footprint "eagle-import:R1206")
      (libsource (lib "eagle-import") (part "rcl_334_R-US_R1206"))
    )
    (comp (ref "R26")
      (value "330E")
      (footprint "eagle-import:R0603")
      (libsource (lib "eagle-import") (part "R-US_R0603"))
    )
    (comp (ref "R27")
      (value "1K")
      (footprint "eagle-import:R0603")
      (libsource (lib "eagle-import") (part "R-US_R0603"))
    )
    (comp (ref "R34")
      (value "220E")
      (footprint "eagle-import:R1206")
      (libsource (lib "eagle-import") (part "rcl_334_R-US_R1206"))
    )
    (comp (ref "S2")
      (value "3006.2115")
      (footprint "eagle-import:30062115")
      (fields (field (name "MOUSER_PART_NUMBER") "979-3006.2115"))
      (libsource (lib "eagle-import") (part "3006.2115"))
    )
    (comp (ref "U$1")
      (value "FIDUCIALMOUNT")
      (footprint "eagle-import:FIDUCIA-MOUNT")
      (libsource (lib "eagle-import") (part "FIDUCIALMOUNT"))
    )
    (comp (ref "U$2")
      (value "FIDUCIALMOUNT")
      (footprint "eagle-import:FIDUCIA-MOUNT")
      (libsource (lib "eagle-import") (part "FIDUCIALMOUNT"))
    )
    (comp (ref "U$3")
      (value "FIDUCIALMOUNT")
      (footprint "eagle-import:FIDUCIA-MOUNT")
      (libsource (lib "eagle-import") (part "FIDUCIALMOUNT"))
    )
    (comp (ref "+5V")
      (value "TPTP10R")
      (footprint "eagle-import:TP10R")
      (libsource (lib "eagle-import") (part "TPTP10R"))
    )
    (comp (ref "+HV")
      (value "TPTP10R")
      (footprint "eagle-import:TP10R")
      (libsource (lib "eagle-import") (part "TPTP10R"))
    )
    (comp (ref "-5V")
      (value "TPTP10R")
      (footprint "eagle-import:TP10R")
      (libsource (lib "eagle-import") (part "TPTP10R"))
    )
    (comp (ref "-HV")
      (value "TPTP10R")
      (footprint "eagle-import:TP10R")
      (libsource (lib "eagle-import") (part "TPTP10R"))
    )
    (comp (ref "3.3V")
      (value "TPTP10R")
      (footprint "eagle-import:TP10R")
      (libsource (lib "eagle-import") (part "TPTP10R"))
    )
    (comp (ref "AGND")
      (value "TPTP10R")
      (footprint "eagle-import:TP10R")
      (libsource (lib "eagle-import") (part "TPTP10R"))
    )
    (comp (ref "C25")
      (value "0.1uF")
      (footprint "eagle-import:C1206")
      (libsource (lib "eagle-import") (part "C-USC1206"))
    )
    (comp (ref "C26")
      (value "1uF")
      (footprint "eagle-import:C0805")
      (libsource (lib "eagle-import") (part "rcl_334_C-USC0805"))
    )
    (comp (ref "C27")
      (value "10uF")
      (footprint "eagle-import:C0805")
      (libsource (lib "eagle-import") (part "rcl_334_C-USC0805"))
    )
    (comp (ref "C28")
      (value "10nF")
      (footprint "eagle-import:C1206")
      (libsource (lib "eagle-import") (part "C-USC1206"))
    )
    (comp (ref "C29")
      (value "47uF")
      (footprint "eagle-import:PANASONIC_D")
      (libsource (lib "eagle-import") (part "0113_47UF"))
    )
    (comp (ref "C30")
      (value "4.7uF")
      (footprint "eagle-import:CAPPM7343X310N")
      (fields
        (field (name "MANUFACTURER_PART_NUMBER") "593D475X9050D2TE3")
        (field (name "MOUSER_PART_NUMBER") "74-593D475X9050D2TE3")
      )
      (libsource (lib "eagle-import") (part "593D475X9050D2TE3"))
    )
    (comp (ref "C31")
      (value "1uF")
      (footprint "eagle-import:C0805")
      (libsource (lib "eagle-import") (part "rcl_334_C-USC0805"))
    )
    (comp (ref "C32")
      (value "1uF")
      (footprint "eagle-import:C0805")
      (libsource (lib "eagle-import") (part "rcl_334_C-USC0805"))
    )
    (comp (ref "C33")
      (value "4.7uF")
      (footprint "eagle-import:CAPPM7343X310N")
      (fields
        (field (name "MANUFACTURER_PART_NUMBER") "593D475X9050D2TE3")
        (field (name "MOUSER_PART_NUMBER") "74-593D475X9050D2TE3")
      )
      (libsource (lib "eagle-import") (part "593D475X9050D2TE3"))
    )
    (comp (ref "C34")
      (value "4.7uF")
      (footprint "eagle-import:CAPPM7343X310N")
      (fields
        (field (name "MANUFACTURER_PART_NUMBER") "593D475X9050D2TE3")
        (field (name "MOUSER_PART_NUMBER") "74-593D475X9050D2TE3")
      )
      (libsource (lib "eagle-import") (part "593D475X9050D2TE3"))
    )
    (comp (ref "D2")
      (value "SS1P3L")
      (footprint "eagle-import:DO220AAL")
      (fields (field (name "PART_NUMBER") "SS1P3L-M3/84A"))
      (libsource (lib "eagle-import") (part "0025_SS1P3L-M3/84A"))
    )
    (comp (ref "D3")
      (value "MSS1P3L-M3/89A")
      (footprint "eagle-import:MICROSMP")
      (libsource (lib "eagle-import") (part "1653_MSS1P3L-M3/89A"))
    )
    (comp (ref "D4")
      (value "LSM115JE3_TR13")
      (footprint "eagle-import:DIOM5436X330N")
      (fields
        (field (name "ARROW_PART_NUMBER") "LSM115JE3/TR13")
        (field (name "MOUSER_PART_NUMBER") "494-LSM115JE3/TR13")
      )
      (libsource (lib "eagle-import") (part "LSM115JE3_TR13"))
    )
    (comp (ref "DGND")
      (value "TPTP10R")
      (footprint "eagle-import:TP10R")
      (libsource (lib "eagle-import") (part "TPTP10R"))
    )
    (comp (ref "IC13")
      (value "TPS73633DBVR")
      (footprint "eagle-import:SOT95P280X145-5N")
      (fields (field (name "MOUSER_PART_NUMBER") "595-TPS73633DBVR"))
      (libsource (lib "eagle-import") (part "TPS73633DBVR"))
    )
    (comp (ref "IC14")
      (value "MIC3975-5.0YMM-TR")
      (footprint "eagle-import:SOP65P490X109-8N")
      (libsource (lib "eagle-import") (part "MIC3975-5.0YMM-TR"))
    )
    (comp (ref "J7")
      (value "CON-SOCJ-2155")
      (footprint "eagle-import:CONSOCJ2155")
      (fields (field (name "MOUSER_PART_NUMBER") "992-CON-SOCJ-2155"))
      (libsource (lib "eagle-import") (part "CON-SOCJ-2155"))
    )
    (comp (ref "L1")
      (value "MH2029-300Y")
      (footprint "eagle-import:0805")
      (fields (field (name "PART_NUMBER") "BLM21PG300SN1D_/_MH2029-300Y"))
      (libsource (lib "eagle-import") (part "0001_BLM21PG300SN1D_/_MH2029-300Y"))
    )
    (comp (ref "PS1")
      (value "NMT0572SC")
      (footprint "eagle-import:NMT1272SC")
      (fields (field (name "MOUSER_PART_NUMBER") "580-NMT0572SC"))
      (libsource (lib "eagle-import") (part "NMT0572SC"))
    )
    (comp (ref "PS2")
      (value "NMT0572SC")
      (footprint "eagle-import:NMT1272SC")
      (fields (field (name "MOUSER_PART_NUMBER") "580-NMT0572SC"))
      (libsource (lib "eagle-import") (part "NMT0572SC"))
    )
    (comp (ref "R32")
      (value "100K")
      (footprint "eagle-import:R1206")
      (libsource (lib "eagle-import") (part "rcl_334_R-US_R1206"))
    )
    (comp (ref "R33")
      (value "470K")
      (footprint "eagle-import:R1206")
      (libsource (lib "eagle-import") (part "rcl_334_R-US_R1206"))
    )
    (comp (ref "S3")
      (value "1101M2S3CQE2")
      (footprint "eagle-import:1000-SERIES(SPDT)")
      (fields (field (name "MOUSER_PART_NUMBER") "611-1101M2S3CQE2"))
      (libsource (lib "eagle-import") (part "1101M2S3CQE2"))
    )
    (comp (ref "U6")
      (value "LTC4412HS6TRMPBF")
      (footprint "eagle-import:TSOT-23_S6_ADI")
      (fields
        (field (name "MANUFACTURER_PART_NUMBER") "LTC4412HS6#TRMPBF")
        (field (name "COPYRIGHT") "Copyright (C) 2018 Accelerated Designs. All rights reserved")
      )
      (libsource (lib "eagle-import") (part "LTC4412HS6TRMPBF"))
    )
    (comp (ref "U7")
      (value "PMV48XP,215TO-236_SOT23_NEX-L")
      (footprint "eagle-import:TO-236_SOT23_NEX-L")
      (fields
        (field (name "MANUFACTURER_PART_NUMBER") "PMV48XP,215")
        (field (name "COPYRIGHT") "Copyright (C) 2018 Accelerated Designs. All rights reserved")
      )
      (libsource (lib "eagle-import") (part "PMV48XP,215TO-236_SOT23_NEX-L"))
    )
    (comp (ref "U8")
      (value "PDME1-S5-D5-S")
      (footprint "eagle-import:CONV_PDME1-S5-D5-S")
      (fields (field (name "MF") "CUI"))
      (libsource (lib "eagle-import") (part "PDME1-S5-D5-S"))
    )
    (comp (ref "VIN5V")
      (value "TPTP10R")
      (footprint "eagle-import:TP10R")
      (libsource (lib "eagle-import") (part "TPTP10R"))
    )
  )
  (nets
    (net (code "1") (name "+3V3") (class "Default")
      (node (ref "3.3V") (pin "TP") (pinfunction "TP_TP") (pintype "input"))
      (node (ref "C19") (pin "1") (pinfunction "1_1") (pintype "passive"))
      (node (ref "C3") (pin "1") (pinfunction "1_1") (pintype "passive"))
      (node (ref "C4") (pin "1") (pinfunction "1_1") (pintype "passive"))
      (node (ref "C5") (pin "1") (pinfunction "1_1") (pintype "passive"))
      (node (ref "IC1") (pin "10") (pinfunction "VDD_1_10") (pintype "bidirectional"))
      (node (ref "IC1") (pin "19") (pinfunction "AVDD_19") (pintype "bidirectional"))
      (node (ref "IC1") (pin "26") (pinfunction "VDD_2_26") (pintype "bidirectional"))
      (node (ref "IC1") (pin "38") (pinfunction "VDD_3_38") (pintype "bidirectional"))
      (node (ref "IC1") (pin "57") (pinfunction "VDD_4_57") (pintype "bidirectional"))
      (node (ref "IC13") (pin "5") (pinfunction "OUT_5") (pintype "bidirectional"))
      (node (ref "J1") (pin "2") (pinfunction "S_2") (pintype "passive"))
      (node (ref "R1") (pin "2") (pinfunction "2_2") (pintype "passive"))
      (node (ref "R17") (pin "2") (pinfunction "2_2") (pintype "passive"))
      (node (ref "R3") (pin "1") (pinfunction "1_1") (pintype "passive"))
      (node (ref "R36") (pin "2") (pinfunction "2_2") (pintype "passive"))
      (node (ref "R37") (pin "2") (pinfunction "2_2") (pintype "passive"))
      (node (ref "R4") (pin "1") (pinfunction "1_1") (pintype "passive"))
      (node (ref "R8") (pin "1") (pinfunction "1_1") (pintype "passive"))
      (node (ref "S2") (pin "3") (pinfunction "A_3") (pintype "bidirectional"))
      (node (ref "U4") (pin "1") (pinfunction "VL_1") (pintype "power_in"))
      (node (ref "U4") (pin "7") (pinfunction "~{SHDN}_7") (pintype "input"))
      (node (ref "U5") (pin "1") (pinfunction "VL_1") (pintype "power_in"))
      (node (ref "U5") (pin "7") (pinfunction "~{SHDN}_7") (pintype "input"))
    )
    (net (code "2") (name "+5V") (class "Default")
      (node (ref "+5V") (pin "TP") (pinfunction "TP_TP") (pintype "input"))
      (node (ref "C10") (pin "1") (pinfunction "+_1") (pintype "bidirectional"))
      (node (ref "C14") (pin "1") (pinfunction "1_1") (pintype "passive"))
      (node (ref "C17") (pin "1") (pinfunction "+_1") (pintype "bidirectional"))
      (node (ref "C21") (pin "1") (pinfunction "1_1") (pintype "passive"))
      (node (ref "C34") (pin "1") (pinfunction "+_1") (pintype "bidirectional"))
      (node (ref "C7") (pin "1") (pinfunction "1_1") (pintype "passive"))
      (node (ref "C8") (pin "1") (pinfunction "1_1") (pintype "passive"))
      (node (ref "IC3") (pin "8") (pinfunction "VCC_8") (pintype "power_in"))
      (node (ref "IC4") (pin "8") (pinfunction "VCC_8") (pintype "power_in"))
      (node (ref "IC6") (pin "6") (pinfunction "VCC_6") (pintype "bidirectional"))
      (node (ref "R9") (pin "1") (pinfunction "1_1") (pintype "passive"))
      (node (ref "U1") (pin "8") (pinfunction "V+_8") (pintype "power_in"))
      (node (ref "U2") (pin "7") (pinfunction "VCC_7") (pintype "power_in"))
      (node (ref "U3") (pin "7") (pinfunction "VCC_7") (pintype "power_in"))
      (node (ref "U4") (pin "14") (pinfunction "V+_14") (pintype "power_in"))
      (node (ref "U5") (pin "14") (pinfunction "V+_14") (pintype "power_in"))
      (node (ref "U8") (pin "6") (pinfunction "+VOUT_6") (pintype "output"))
      (node (ref "U9") (pin "1") (pinfunction "IN_1") (pintype "input"))
    )
    (net (code "3") (name "-5V") (class "Default")
      (node (ref "-5V") (pin "TP") (pinfunction "TP_TP") (pintype "input"))
      (node (ref "C13") (pin "2") (pinfunction "2_2") (pintype "passive"))
      (node (ref "C18") (pin "2") (pinfunction "-_2") (pintype "bidirectional"))
      (node (ref "C33") (pin "2") (pinfunction "-_2") (pintype "bidirectional"))
      (node (ref "C9") (pin "2") (pinfunction "-_2") (pintype "bidirectional"))
      (node (ref "U1") (pin "4") (pinfunction "V-_4") (pintype "power_in"))
      (node (ref "U2") (pin "4") (pinfunction "VEE_4") (pintype "power_in"))
      (node (ref "U3") (pin "4") (pinfunction "VEE_4") (pintype "power_in"))
      (node (ref "U4") (pin "10") (pinfunction "V-_10") (pintype "power_in"))
      (node (ref "U5") (pin "10") (pinfunction "V-_10") (pintype "power_in"))
      (node (ref "U8") (pin "4") (pinfunction "-VOUT_4") (pintype "output"))
    )
    (net (code "4") (name "AD3") (class "Default")
      (node (ref "JP7") (pin "4") (pinfunction "4_4") (pintype "passive"))
    )
    (net (code "5") (name "AD4") (class "Default")
      (node (ref "JP7") (pin "5") (pinfunction "5_5") (pintype "passive"))
    )
    (net (code "6") (name "AD5") (class "Default")
      (node (ref "JP7") (pin "6") (pinfunction "6_6") (pintype "passive"))
    )
    (net (code "7") (name "AD6") (class "Default")
      (node (ref "JP7") (pin "7") (pinfunction "7_7") (pintype "passive"))
    )
    (net (code "8") (name "AD7") (class "Default")
      (node (ref "JP7") (pin "8") (pinfunction "8_8") (pintype "passive"))
    )
    (net (code "9") (name "AD8") (class "Default")
      (node (ref "JP8") (pin "1") (pinfunction "1_1") (pintype "passive"))
    )
    (net (code "10") (name "AD9") (class "Default")
      (node (ref "JP8") (pin "2") (pinfunction "2_2") (pintype "passive"))
    )
    (net (code "11") (name "AD10") (class "Default")
      (node (ref "JP8") (pin "3") (pinfunction "3_3") (pintype "passive"))
    )
    (net (code "12") (name "AD11(TXD3)") (class "Default")
      (node (ref "JP8") (pin "4") (pinfunction "4_4") (pintype "passive"))
    )
    (net (code "13") (name "AGND") (class "Default")
      (node (ref "AGND") (pin "TP") (pinfunction "TP_TP") (pintype "input"))
      (node (ref "C10") (pin "2") (pinfunction "-_2") (pintype "bidirectional"))
      (node (ref "C11") (pin "2") (pinfunction "2_2") (pintype "passive"))
      (node (ref "C13") (pin "1") (pinfunction "1_1") (pintype "passive"))
      (node (ref "C14") (pin "2") (pinfunction "2_2") (pintype "passive"))
      (node (ref "C17") (pin "2") (pinfunction "-_2") (pintype "bidirectional"))
      (node (ref "C18") (pin "1") (pinfunction "+_1") (pintype "bidirectional"))
      (node (ref "C21") (pin "2") (pinfunction "2_2") (pintype "passive"))
      (node (ref "C31") (pin "1") (pinfunction "1_1") (pintype "passive"))
      (node (ref "C32") (pin "2") (pinfunction "2_2") (pintype "passive"))
      (node (ref "C33") (pin "1") (pinfunction "+_1") (pintype "bidirectional"))
      (node (ref "C34") (pin "2") (pinfunction "-_2") (pintype "bidirectional"))
      (node (ref "C35") (pin "2") (pinfunction "2_2") (pintype "passive"))
      (node (ref "C36") (pin "2") (pinfunction "2_2") (pintype "passive"))
      (node (ref "C37") (pin "2") (pinfunction "2_2") (pintype "passive"))
      (node (ref "C38") (pin "2") (pinfunction "2_2") (pintype "passive"))
      (node (ref "C7") (pin "2") (pinfunction "2_2") (pintype "passive"))
      (node (ref "C8") (pin "2") (pinfunction "2_2") (pintype "passive"))
      (node (ref "C9") (pin "1") (pinfunction "+_1") (pintype "bidirectional"))
      (node (ref "IC3") (pin "5") (pinfunction "GND_5") (pintype "power_in"))
      (node (ref "IC4") (pin "5") (pinfunction "GND_5") (pintype "power_in"))
      (node (ref "IC5") (pin "2") (pinfunction "-IN_2") (pintype "input"))
      (node (ref "IC6") (pin "1") (pinfunction "IN-_1") (pintype "bidirectional"))
      (node (ref "IC6") (pin "2") (pinfunction "GND_2") (pintype "bidirectional"))
      (node (ref "IC6") (pin "4") (pinfunction "SHDN_4") (pintype "bidirectional"))
      (node (ref "IC8") (pin "2") (pinfunction "-IN_2") (pintype "input"))
      (node (ref "J5") (pin "2") (pinfunction "2_2") (pintype "bidirectional"))
      (node (ref "J6") (pin "2") (pinfunction "2_2") (pintype "bidirectional"))
      (node (ref "PS1") (pin "5") (pinfunction "+VOUT_5") (pintype "bidirectional"))
      (node (ref "PS2") (pin "8") (pinfunction "-VOUT3_8") (pintype "bidirectional"))
      (node (ref "R10") (pin "1") (pinfunction "1_1") (pintype "passive"))
      (node (ref "R25") (pin "2") (pinfunction "2_2") (pintype "passive"))
      (node (ref "U4") (pin "11") (pinfunction "P0B_11") (pintype "bidirectional"))
      (node (ref "U5") (pin "11") (pinfunction "P0B_11") (pintype "bidirectional"))
      (node (ref "U8") (pin "5") (pinfunction "0V_5") (pintype "power_in"))
      (node (ref "U9") (pin "3") (pinfunction "GND_3") (pintype "power_in"))
    )
    (net (code "14") (name "AREF") (class "Default")
      (node (ref "JP3") (pin "8") (pinfunction "8_8") (pintype "passive"))
    )
    (net (code "15") (name "BD+") (class "Default")
      (node (ref "IC2") (pin "15") (pinfunction "USBDP_15") (pintype "bidirectional"))
      (node (ref "J2") (pin "3") (pinfunction "D+_3") (pintype "bidirectional"))
      (node (ref "TP1") (pin "X") (pinfunction "P$1_X") (pintype "passive"))
    )
    (net (code "16") (name "BD-") (class "Default")
      (node (ref "IC2") (pin "16") (pinfunction "USBDM_16") (pintype "bidirectional"))
      (node (ref "J2") (pin "2") (pinfunction "D-_2") (pintype "bidirectional"))
      (node (ref "TP2") (pin "X") (pinfunction "P$1_X") (pintype "passive"))
    )
    (net (code "17") (name "CANRX0") (class "Default")
      (node (ref "JP8") (pin "7") (pinfunction "7_7") (pintype "passive"))
    )
    (net (code "18") (name "CANTX0") (class "Default")
      (node (ref "JP8") (pin "8") (pinfunction "8_8") (pintype "passive"))
    )
    (net (code "19") (name "CH1_EN~{}") (class "Default")
      (node (ref "IC1") (pin "15") (pinfunction "PGEC3/AN1/VREF-/CN3/RB1_15") (pintype "bidirectional"))
      (node (ref "K1") (pin "2") (pinfunction "-_CONTROL_-_SWITCH_#1_2") (pintype "bidirectional"))
    )
    (net (code "20") (name "CH2_EN~{}") (class "Default")
      (node (ref "IC1") (pin "14") (pinfunction "AN2/~{SS1}/CN4/RB2_14") (pintype "bidirectional"))
      (node (ref "K1") (pin "4") (pinfunction "-_CONTROL_-_SWITCH_#2_4") (pintype "bidirectional"))
    )
    (net (code "21") (name "COMM_RET") (class "Default")
      (node (ref "IC6") (pin "8") (pinfunction "IN+_8") (pintype "bidirectional"))
      (node (ref "J3") (pin "2") (pinfunction "2_2") (pintype "passive"))
      (node (ref "J4") (pin "2") (pinfunction "2_2") (pintype "passive"))
      (node (ref "R10") (pin "2") (pinfunction "2_2") (pintype "passive"))
      (node (ref "R16") (pin "2") (pinfunction "2_2") (pintype "passive"))
      (node (ref "R23") (pin "2") (pinfunction "2_2") (pintype "passive"))
    )
    (net (code "22") (name "CS_DIGIPOT1") (class "Default")
      (node (ref "CS1") (pin "TP") (pinfunction "TP_TP") (pintype "input"))
      (node (ref "IC1") (pin "8") (pinfunction "~{SS2}/CN11/RG9_8") (pintype "bidirectional"))
      (node (ref "U5") (pin "3") (pinfunction "~{CS}_3") (pintype "input"))
    )
    (net (code "23") (name "CS_DIGIPOT2") (class "Default")
      (node (ref "CS2") (pin "TP") (pinfunction "TP_TP") (pintype "input"))
      (node (ref "IC1") (pin "18") (pinfunction "PGED1/AN7/RB7_18") (pintype "bidirectional"))
      (node (ref "U4") (pin "3") (pinfunction "~{CS}_3") (pintype "input"))
    )
    (net (code "24") (name "D9") (class "Default")
      (node (ref "IC1") (pin "43") (pinfunction "IC2/~{U1CTS}/INT2/RD9_43") (pintype "bidirectional"))
      (node (ref "JP3") (pin "2") (pinfunction "2_2") (pintype "passive"))
      (node (ref "R26") (pin "2") (pinfunction "2_2") (pintype "passive"))
    )
    (net (code "25") (name "D10") (class "Default")
      (node (ref "IC1") (pin "42") (pinfunction "IC1/INT1/RD8_42") (pintype "bidirectional"))
      (node (ref "JP3") (pin "3") (pinfunction "3_3") (pintype "passive"))
      (node (ref "R27") (pin "2") (pinfunction "2_2") (pintype "passive"))
    )
    (net (code "26") (name "DAC0(CANRX1)") (class "Default")
      (node (ref "JP8") (pin "5") (pinfunction "5_5") (pintype "passive"))
    )
    (net (code "27") (name "DAC1") (class "Default")
      (node (ref "JP8") (pin "6") (pinfunction "6_6") (pintype "passive"))
    )
    (net (code "28") (name "DC_5V") (class "Default")
      (node (ref "C27") (pin "1") (pinfunction "1_1") (pintype "passive"))
      (node (ref "IC14") (pin "4") (pinfunction "OUT_4") (pintype "bidirectional"))
      (node (ref "R32") (pin "1") (pinfunction "1_1") (pintype "passive"))
      (node (ref "U6") (pin "1") (pinfunction "VIN_1") (pintype "power_in"))
      (node (ref "U7") (pin "3") (pinfunction "D_3") (pintype "passive"))
    )
    (net (code "29") (name "EOFF_R~{}") (class "Default")
      (node (ref "IC1") (pin "16") (pinfunction "PGED3/AN0/VREF+/CN2/RB0_16") (pintype "bidirectional"))
      (node (ref "Q8") (pin "1") (pinfunction "B_1") (pintype "bidirectional"))
    )
    (net (code "30") (name "ERR_FLG") (class "Default")
      (node (ref "IC1") (pin "44") (pinfunction "IC3/INT3/RD10_44") (pintype "bidirectional"))
      (node (ref "IC14") (pin "3") (pinfunction "FLG_3") (pintype "bidirectional"))
      (node (ref "R32") (pin "2") (pinfunction "2_2") (pintype "passive"))
    )
    (net (code "31") (name "GND") (class "Default")
      (node (ref "C1") (pin "2") (pinfunction "2_2") (pintype "passive"))
      (node (ref "C19") (pin "2") (pinfunction "2_2") (pintype "passive"))
      (node (ref "C2") (pin "2") (pinfunction "-_2") (pintype "bidirectional"))
      (node (ref "C25") (pin "2") (pinfunction "2_2") (pintype "passive"))
      (node (ref "C26") (pin "2") (pinfunction "2_2") (pintype "passive"))
      (node (ref "C27") (pin "2") (pinfunction "2_2") (pintype "passive"))
      (node (ref "C28") (pin "2") (pinfunction "2_2") (pintype "passive"))
      (node (ref "C29") (pin "-") (pinfunction "-_-") (pintype "passive"))
      (node (ref "C3") (pin "2") (pinfunction "2_2") (pintype "passive"))
      (node (ref "C30") (pin "2") (pinfunction "-_2") (pintype "bidirectional"))
      (node (ref "C4") (pin "2") (pinfunction "2_2") (pintype "passive"))
      (node (ref "C5") (pin "2") (pinfunction "2_2") (pintype "passive"))
      (node (ref "C6") (pin "2") (pinfunction "2_2") (pintype "passive"))
      (node (ref "DGND") (pin "TP") (pinfunction "TP_TP") (pintype "input"))
      (node (ref "IC1") (pin "20") (pinfunction "AVSS_20") (pintype "bidirectional"))
      (node (ref "IC1") (pin "25") (pinfunction "VSS_2_25") (pintype "bidirectional"))
      (node (ref "IC1") (pin "41") (pinfunction "VSS_3_41") (pintype "bidirectional"))
      (node (ref "IC1") (pin "9") (pinfunction "VSS_1_9") (pintype "bidirectional"))
      (node (ref "IC13") (pin "2") (pinfunction "GND_2") (pintype "bidirectional"))
      (node (ref "IC14") (pin "5") (pinfunction "GND_1_5") (pintype "bidirectional"))
      (node (ref "IC14") (pin "6") (pinfunction "GND_2_6") (pintype "bidirectional"))
      (node (ref "IC14") (pin "7") (pinfunction "GND_3_7") (pintype "bidirectional"))
      (node (ref "IC14") (pin "8") (pinfunction "GND_4_8") (pintype "bidirectional"))
      (node (ref "IC2") (pin "18") (pinfunction "GND_18") (pintype "power_in"))
      (node (ref "IC2") (pin "21") (pinfunction "GND_21") (pintype "power_in"))
      (node (ref "IC2") (pin "25") (pinfunction "GND_25") (pintype "power_in"))
      (node (ref "IC2") (pin "26") (pinfunction "TEST_26") (pintype "input"))
      (node (ref "IC2") (pin "7") (pinfunction "GND_7") (pintype "power_in"))
      (node (ref "J1") (pin "3") (pinfunction "S_3") (pintype "passive"))
      (node (ref "J2") (pin "5") (pinfunction "GND_5") (pintype "bidirectional"))
      (node (ref "J7") (pin "2") (pinfunction "2_2") (pintype "bidirectional"))
      (node (ref "J7") (pin "3") (pinfunction "3_3") (pintype "bidirectional"))
      (node (ref "JP3") (pin "7") (pinfunction "7_7") (pintype "passive"))
      (node (ref "JP6") (pin "6") (pinfunction "6_6") (pintype "passive"))
      (node (ref "JP6") (pin "7") (pinfunction "7_7") (pintype "passive"))
      (node (ref "LED5") (pin "C") (pinfunction "C_C") (pintype "passive"))
      (node (ref "LED6") (pin "C") (pinfunction "C_C") (pintype "passive"))
      (node (ref "PS1") (pin "2") (pinfunction "-VIN_2") (pintype "bidirectional"))
      (node (ref "PS2") (pin "2") (pinfunction "-VIN_2") (pintype "bidirectional"))
      (node (ref "Q8") (pin "3") (pinfunction "C_3") (pintype "bidirectional"))
      (node (ref "R25") (pin "1") (pinfunction "1_1") (pintype "passive"))
      (node (ref "S1") (pin "1") (pinfunction "1_1") (pintype "passive"))
      (node (ref "S2") (pin "1") (pinfunction "COM_1") (pintype "bidirectional"))
      (node (ref "TP4") (pin "X") (pinfunction "P$1_X") (pintype "passive"))
      (node (ref "U4") (pin "6") (pinfunction "~{WLAT}_6") (pintype "input"))
      (node (ref "U4") (pin "9") (pinfunction "DGND_9") (pintype "power_in"))
      (node (ref "U5") (pin "6") (pinfunction "~{WLAT}_6") (pintype "input"))
      (node (ref "U5") (pin "9") (pinfunction "DGND_9") (pintype "power_in"))
      (node (ref "U6") (pin "2") (pinfunction "GND_2") (pintype "passive"))
      (node (ref "U6") (pin "3") (pinfunction "CTL_3") (pintype "input"))
      (node (ref "U8") (pin "2") (pinfunction "GND_2") (pintype "power_in"))
    )
    (net (code "32") (name "INT0") (class "Default")
      (node (ref "IC1") (pin "35") (pinfunction "~{U1RTS}/SCK1/INT0/RF6_35") (pintype "bidirectional"))
      (node (ref "R17") (pin "1") (pinfunction "1_1") (pintype "passive"))
      (node (ref "S2") (pin "2") (pinfunction "NO_2") (pintype "bidirectional"))
    )
    (net (code "33") (name "IOUT") (class "Default")
      (node (ref "IC1") (pin "22") (pinfunction "AN9/RB9_22") (pintype "bidirectional"))
      (node (ref "JP7") (pin "1") (pinfunction "1_1") (pintype "passive"))
      (node (ref "R24") (pin "1") (pinfunction "1_1") (pintype "passive"))
    )
    (net (code "34") (name "MASTER-RESET") (class "Default")
      (node (ref "C1") (pin "1") (pinfunction "1_1") (pintype "passive"))
      (node (ref "JP6") (pin "3") (pinfunction "3_3") (pintype "passive"))
      (node (ref "R1") (pin "1") (pinfunction "1_1") (pintype "passive"))
      (node (ref "R2") (pin "1") (pinfunction "1_1") (pintype "passive"))
      (node (ref "S1") (pin "3") (pinfunction "2_3") (pintype "passive"))
    )
    (net (code "35") (name "Net-(C2-+)") (class "Default")
      (node (ref "C2") (pin "1") (pinfunction "+_1") (pintype "bidirectional"))
      (node (ref "IC1") (pin "56") (pinfunction "VCAP_56") (pintype "bidirectional"))
    )
    (net (code "36") (name "Net-(C11-Pad1)") (class "Default")
      (node (ref "C11") (pin "1") (pinfunction "1_1") (pintype "passive"))
      (node (ref "R24") (pin "2") (pinfunction "2_2") (pintype "passive"))
      (node (ref "R28") (pin "2") (pinfunction "2_2") (pintype "passive"))
    )
    (net (code "37") (name "Net-(D2-A)") (class "Default")
      (node (ref "D2") (pin "P$2") (pinfunction "A_P$2") (pintype "bidirectional"))
      (node (ref "D3") (pin "A") (pinfunction "A_A") (pintype "passive"))
      (node (ref "L1") (pin "1") (pinfunction "1_1") (pintype "passive"))
    )
    (net (code "38") (name "Net-(D5-A)") (class "Default")
      (node (ref "D5") (pin "2") (pinfunction "A_2") (pintype "bidirectional"))
      (node (ref "JP6") (pin "5") (pinfunction "5_5") (pintype "passive"))
    )
    (net (code "39") (name "Net-(D6-Pad2)") (class "Default")
      (node (ref "D6") (pin "2") (pinfunction "2_2") (pintype "passive"))
      (node (ref "R13") (pin "1") (pinfunction "1_1") (pintype "passive"))
    )
    (net (code "40") (name "Net-(D7-Pad1)") (class "Default")
      (node (ref "D7") (pin "1") (pinfunction "1_1") (pintype "passive"))
      (node (ref "R12") (pin "2") (pinfunction "2_2") (pintype "passive"))
    )
    (net (code "41") (name "Net-(D8-Pad2)") (class "Default")
      (node (ref "D8") (pin "2") (pinfunction "2_2") (pintype "passive"))
      (node (ref "R20") (pin "1") (pinfunction "1_1") (pintype "passive"))
    )
    (net (code "42") (name "Net-(D9-Pad1)") (class "Default")
      (node (ref "D9") (pin "1") (pinfunction "1_1") (pintype "passive"))
      (node (ref "R19") (pin "2") (pinfunction "2_2") (pintype "passive"))
    )
    (net (code "43") (name "Net-(F2-Pad2)") (class "Default")
      (node (ref "F2") (pin "2") (pinfunction "2_2") (pintype "bidirectional"))
      (node (ref "J3") (pin "1") (pinfunction "1_1") (pintype "passive"))
    )
    (net (code "44") (name "Net-(F3-Pad2)") (class "Default")
      (node (ref "F3") (pin "2") (pinfunction "2_2") (pintype "bidirectional"))
      (node (ref "J4") (pin "1") (pinfunction "1_1") (pintype "passive"))
    )
    (net (code "45") (name "Net-(IC2-3V3OUT)") (class "Default")
      (node (ref "IC2") (pin "17") (pinfunction "3V3OUT_17") (pintype "output"))
      (node (ref "IC2") (pin "4") (pinfunction "VCCIO_4") (pintype "power_in"))
    )
    (net (code "46") (name "Net-(IC2-CBUS0)") (class "Default")
      (node (ref "IC2") (pin "23") (pinfunction "CBUS0_23") (pintype "bidirectional"))
      (node (ref "LED2") (pin "C") (pinfunction "C_C") (pintype "passive"))
    )
    (net (code "47") (name "Net-(IC2-CBUS1)") (class "Default")
      (node (ref "IC2") (pin "22") (pinfunction "CBUS1_22") (pintype "bidirectional"))
      (node (ref "LED1") (pin "C") (pinfunction "C_C") (pintype "passive"))
    )
    (net (code "48") (name "Net-(IC2-CBUS3)") (class "Default")
      (node (ref "IC2") (pin "14") (pinfunction "CBUS3_14") (pintype "bidirectional"))
      (node (ref "R6") (pin "1") (pinfunction "1_1") (pintype "passive"))
    )
    (net (code "49") (name "Net-(IC3-V01)") (class "Default")
      (node (ref "IC3") (pin "7") (pinfunction "V01_7") (pintype "bidirectional"))
      (node (ref "R9") (pin "2") (pinfunction "2_2") (pintype "passive"))
      (node (ref "U2") (pin "1") (pinfunction "P1_1") (pintype "input"))
    )
    (net (code "50") (name "Net-(IC3-V02)") (class "Default")
      (node (ref "IC3") (pin "6") (pinfunction "V02_6") (pintype "bidirectional"))
      (node (ref "R9") (pin "3") (pinfunction "3_3") (pintype "passive"))
      (node (ref "U2") (pin "10") (pinfunction "M1_10") (pintype "input"))
    )
    (net (code "51") (name "Net-(IC3-VF1+)") (class "Default")
      (node (ref "IC3") (pin "1") (pinfunction "VF1+_1") (pintype "bidirectional"))
      (node (ref "R8") (pin "3") (pinfunction "3_3") (pintype "passive"))
    )
    (net (code "52") (name "Net-(IC3-VF2+)") (class "Default")
      (node (ref "IC3") (pin "4") (pinfunction "VF2+_4") (pintype "bidirectional"))
      (node (ref "R8") (pin "2") (pinfunction "2_2") (pintype "passive"))
    )
    (net (code "53") (name "Net-(IC4-V01)") (class "Default")
      (node (ref "IC4") (pin "7") (pinfunction "V01_7") (pintype "bidirectional"))
      (node (ref "R9") (pin "4") (pinfunction "4_4") (pintype "passive"))
      (node (ref "U3") (pin "1") (pinfunction "P1_1") (pintype "input"))
    )
    (net (code "54") (name "Net-(IC4-V02)") (class "Default")
      (node (ref "IC4") (pin "6") (pinfunction "V02_6") (pintype "bidirectional"))
      (node (ref "R9") (pin "5") (pinfunction "5_5") (pintype "passive"))
      (node (ref "U3") (pin "10") (pinfunction "M1_10") (pintype "input"))
    )
    (net (code "55") (name "Net-(IC4-VF1+)") (class "Default")
      (node (ref "IC4") (pin "1") (pinfunction "VF1+_1") (pintype "bidirectional"))
      (node (ref "R8") (pin "5") (pinfunction "5_5") (pintype "passive"))
    )
    (net (code "56") (name "Net-(IC4-VF2+)") (class "Default")
      (node (ref "IC4") (pin "4") (pinfunction "VF2+_4") (pintype "bidirectional"))
      (node (ref "R8") (pin "4") (pinfunction "4_4") (pintype "passive"))
    )
    (net (code "57") (name "Net-(IC5-REF_A)") (class "Default")
      (node (ref "IC5") (pin "1") (pinfunction "REF_B_1") (pintype "input"))
      (node (ref "IC5") (pin "5") (pinfunction "REF_A_5") (pintype "input"))
      (node (ref "IC7") (pin "2") (pinfunction "-IN_2") (pintype "input"))
      (node (ref "IC7") (pin "6") (pinfunction "OUT_6") (pintype "output"))
      (node (ref "VF/B1") (pin "TP") (pinfunction "TP_TP") (pintype "input"))
    )
    (net (code "58") (name "Net-(IC5-V+)") (class "Default")
      (node (ref "IC5") (pin "7") (pinfunction "V+_7") (pintype "power_in"))
      (node (ref "IC7") (pin "7") (pinfunction "V+_7") (pintype "bidirectional"))
      (node (ref "Q2") (pin "1") (pinfunction "E_1") (pintype "bidirectional"))
      (node (ref "V1") (pin "TP") (pinfunction "TP_TP") (pintype "input"))
    )
    (net (code "59") (name "Net-(IC5-V-)") (class "Default")
      (node (ref "IC5") (pin "4") (pinfunction "V-_4") (pintype "power_in"))
      (node (ref "IC7") (pin "4") (pinfunction "V-_4") (pintype "bidirectional"))
      (node (ref "Q1") (pin "1") (pinfunction "E_1") (pintype "bidirectional"))
      (node (ref "V2") (pin "TP") (pinfunction "TP_TP") (pintype "input"))
    )
    (net (code "60") (name "Net-(IC5-V_OUT)") (class "Default")
      (node (ref "D6") (pin "1") (pinfunction "1_1") (pintype "passive"))
      (node (ref "D7") (pin "2") (pinfunction "2_2") (pintype "passive"))
      (node (ref "IC5") (pin "6") (pinfunction "V_OUT_6") (pintype "output"))
      (node (ref "R15") (pin "2") (pinfunction "2_2") (pintype "passive"))
    )
    (net (code "61") (name "Net-(IC6-OUT)") (class "Default")
      (node (ref "IC6") (pin "5") (pinfunction "OUT_5") (pintype "bidirectional"))
      (node (ref "R28") (pin "1") (pinfunction "1_1") (pintype "passive"))
    )
    (net (code "62") (name "Net-(IC6-VREF1)") (class "Default")
      (node (ref "1.6V") (pin "TP") (pinfunction "TP_TP") (pintype "input"))
      (node (ref "IC6") (pin "3") (pinfunction "VREF2_3") (pintype "bidirectional"))
      (node (ref "IC6") (pin "7") (pinfunction "VREF1_7") (pintype "bidirectional"))
      (node (ref "U9") (pin "2") (pinfunction "OUT_2") (pintype "output"))
    )
    (net (code "63") (name "Net-(IC7-+IN)") (class "Default")
      (node (ref "F2") (pin "1") (pinfunction "1_1") (pintype "bidirectional"))
      (node (ref "IC7") (pin "3") (pinfunction "+IN_3") (pintype "input"))
      (node (ref "K1") (pin "8") (pinfunction "LOAD_-_SWITCH_#1_2_8") (pintype "bidirectional"))
      (node (ref "R15") (pin "1") (pinfunction "1_1") (pintype "passive"))
    )
    (net (code "64") (name "Net-(IC8-V_OUT)") (class "Default")
      (node (ref "D8") (pin "1") (pinfunction "1_1") (pintype "passive"))
      (node (ref "D9") (pin "2") (pinfunction "2_2") (pintype "passive"))
      (node (ref "IC8") (pin "6") (pinfunction "V_OUT_6") (pintype "output"))
      (node (ref "R22") (pin "2") (pinfunction "2_2") (pintype "passive"))
    )
    (net (code "65") (name "Net-(IC10-+IN)") (class "Default")
      (node (ref "F3") (pin "1") (pinfunction "1_1") (pintype "bidirectional"))
      (node (ref "IC10") (pin "3") (pinfunction "+IN_3") (pintype "input"))
      (node (ref "K1") (pin "6") (pinfunction "LOAD_-_SWITCH_#2_2_6") (pintype "bidirectional"))
      (node (ref "R22") (pin "1") (pinfunction "1_1") (pintype "passive"))
    )
    (net (code "66") (name "Net-(IC10--IN)") (class "Default")
      (node (ref "IC10") (pin "2") (pinfunction "-IN_2") (pintype "input"))
      (node (ref "IC10") (pin "6") (pinfunction "OUT_6") (pintype "output"))
      (node (ref "IC8") (pin "1") (pinfunction "REF_B_1") (pintype "input"))
      (node (ref "IC8") (pin "5") (pinfunction "REF_A_5") (pintype "input"))
      (node (ref "VF/B2") (pin "TP") (pinfunction "TP_TP") (pintype "input"))
    )
    (net (code "67") (name "Net-(IC10-V+)") (class "Default")
      (node (ref "IC10") (pin "7") (pinfunction "V+_7") (pintype "bidirectional"))
      (node (ref "IC8") (pin "7") (pinfunction "V+_7") (pintype "power_in"))
      (node (ref "Q4") (pin "1") (pinfunction "E_1") (pintype "bidirectional"))
      (node (ref "V3") (pin "TP") (pinfunction "TP_TP") (pintype "input"))
    )
    (net (code "68") (name "Net-(IC10-V-)") (class "Default")
      (node (ref "IC10") (pin "4") (pinfunction "V-_4") (pintype "bidirectional"))
      (node (ref "IC8") (pin "4") (pinfunction "V-_4") (pintype "power_in"))
      (node (ref "Q3") (pin "1") (pinfunction "E_1") (pintype "bidirectional"))
      (node (ref "V4") (pin "TP") (pinfunction "TP_TP") (pintype "input"))
    )
    (net (code "69") (name "Net-(IC13-NR{slash}FB)") (class "Default")
      (node (ref "C28") (pin "1") (pinfunction "1_1") (pintype "passive"))
      (node (ref "IC13") (pin "4") (pinfunction "NR/FB_4") (pintype "bidirectional"))
    )
    (net (code "70") (name "Net-(K1-+_CONTROL_-_SWITCH_#1)") (class "Default")
      (node (ref "K1") (pin "1") (pinfunction "+_CONTROL_-_SWITCH_#1_1") (pintype "bidirectional"))
      (node (ref "R37") (pin "1") (pinfunction "1_1") (pintype "passive"))
    )
    (net (code "71") (name "Net-(K1-+_CONTROL_-_SWITCH_#2)") (class "Default")
      (node (ref "K1") (pin "3") (pinfunction "+_CONTROL_-_SWITCH_#2_3") (pintype "bidirectional"))
      (node (ref "R36") (pin "1") (pinfunction "1_1") (pintype "passive"))
    )
    (net (code "72") (name "Net-(K1-LOAD_-_SWITCH_#1_1)") (class "Default")
      (node (ref "K1") (pin "7") (pinfunction "LOAD_-_SWITCH_#1_1_7") (pintype "bidirectional"))
      (node (ref "R16") (pin "1") (pinfunction "1_1") (pintype "passive"))
    )
    (net (code "73") (name "Net-(K1-LOAD_-_SWITCH_#2_1)") (class "Default")
      (node (ref "K1") (pin "5") (pinfunction "LOAD_-_SWITCH_#2_1_5") (pintype "bidirectional"))
      (node (ref "R23") (pin "1") (pinfunction "1_1") (pintype "passive"))
    )
    (net (code "74") (name "Net-(LED1-PadA)") (class "Default")
      (node (ref "LED1") (pin "A") (pinfunction "A_A") (pintype "passive"))
      (node (ref "R7") (pin "1") (pinfunction "1_1") (pintype "passive"))
    )
    (net (code "75") (name "Net-(LED2-PadA)") (class "Default")
      (node (ref "LED2") (pin "A") (pinfunction "A_A") (pintype "passive"))
      (node (ref "R5") (pin "1") (pinfunction "1_1") (pintype "passive"))
    )
    (net (code "76") (name "Net-(LED5-PadA)") (class "Default")
      (node (ref "LED5") (pin "A") (pinfunction "A_A") (pintype "passive"))
      (node (ref "R26") (pin "1") (pinfunction "1_1") (pintype "passive"))
    )
    (net (code "77") (name "Net-(LED6-PadA)") (class "Default")
      (node (ref "LED6") (pin "A") (pinfunction "A_A") (pintype "passive"))
      (node (ref "R27") (pin "1") (pinfunction "1_1") (pintype "passive"))
    )
    (net (code "78") (name "Net-(PS1-+VIN)") (class "Default")
      (node (ref "PS1") (pin "1") (pinfunction "+VIN_1") (pintype "bidirectional"))
      (node (ref "PS2") (pin "1") (pinfunction "+VIN_1") (pintype "bidirectional"))
      (node (ref "S3") (pin "1") (pinfunction "1_1") (pintype "bidirectional"))
      (node (ref "S3") (pin "2") (pinfunction "2_2") (pintype "bidirectional"))
    )
    (net (code "79") (name "Net-(Q1-B)") (class "Default")
      (node (ref "C39") (pin "2") (pinfunction "2_2") (pintype "passive"))
      (node (ref "Q1") (pin "3") (pinfunction "B_3") (pintype "bidirectional"))
      (node (ref "R11") (pin "2") (pinfunction "2_2") (pintype "passive"))
      (node (ref "R12") (pin "1") (pinfunction "1_1") (pintype "passive"))
    )
    (net (code "80") (name "Net-(Q2-B)") (class "Default")
      (node (ref "C39") (pin "1") (pinfunction "1_1") (pintype "passive"))
      (node (ref "Q2") (pin "3") (pinfunction "B_3") (pintype "bidirectional"))
      (node (ref "R13") (pin "2") (pinfunction "2_2") (pintype "passive"))
      (node (ref "R14") (pin "1") (pinfunction "1_1") (pintype "passive"))
    )
    (net (code "81") (name "Net-(Q3-B)") (class "Default")
      (node (ref "C40") (pin "2") (pinfunction "2_2") (pintype "passive"))
      (node (ref "Q3") (pin "3") (pinfunction "B_3") (pintype "bidirectional"))
      (node (ref "R18") (pin "2") (pinfunction "2_2") (pintype "passive"))
      (node (ref "R19") (pin "1") (pinfunction "1_1") (pintype "passive"))
    )
    (net (code "82") (name "Net-(Q4-B)") (class "Default")
      (node (ref "C40") (pin "1") (pinfunction "1_1") (pintype "passive"))
      (node (ref "Q4") (pin "3") (pinfunction "B_3") (pintype "bidirectional"))
      (node (ref "R20") (pin "2") (pinfunction "2_2") (pintype "passive"))
      (node (ref "R21") (pin "1") (pinfunction "1_1") (pintype "passive"))
    )
    (net (code "83") (name "Net-(Q8-E)") (class "Default")
      (node (ref "Q8") (pin "2") (pinfunction "E_2") (pintype "bidirectional"))
      (node (ref "R34") (pin "1") (pinfunction "1_1") (pintype "passive"))
    )
    (net (code "84") (name "Net-(S2-K)") (class "Default")
      (node (ref "R34") (pin "2") (pinfunction "2_2") (pintype "passive"))
      (node (ref "S2") (pin "4") (pinfunction "K_4") (pintype "bidirectional"))
    )
    (net (code "85") (name "Net-(U1-IN1+)") (class "Default")
      (node (ref "U1") (pin "3") (pinfunction "IN1+_3") (pintype "passive"))
      (node (ref "U5") (pin "12") (pinfunction "P0W_12") (pintype "bidirectional"))
    )
    (net (code "86") (name "Net-(U1-IN2+)") (class "Default")
      (node (ref "U1") (pin "5") (pinfunction "IN2+_5") (pintype "passive"))
      (node (ref "U4") (pin "12") (pinfunction "P0W_12") (pintype "bidirectional"))
    )
    (net (code "87") (name "Net-(U2-OUT)") (class "Default")
      (node (ref "LED4") (pin "1") (pinfunction "1_1") (pintype "passive"))
      (node (ref "U2") (pin "6") (pinfunction "OUT_6") (pintype "output"))
      (node (ref "VO2") (pin "TP") (pinfunction "TP_TP") (pintype "input"))
    )
    (net (code "88") (name "Net-(U2-P3)") (class "Default")
      (node (ref "J6") (pin "1") (pinfunction "1_1") (pintype "bidirectional"))
      (node (ref "U2") (pin "2") (pinfunction "P3_2") (pintype "input"))
    )
    (net (code "89") (name "Net-(U2-REF)") (class "Default")
      (node (ref "J6") (pin "3") (pinfunction "3_3") (pintype "bidirectional"))
      (node (ref "U2") (pin "5") (pinfunction "REF_5") (pintype "input"))
    )
    (net (code "90") (name "Net-(U3-OUT)") (class "Default")
      (node (ref "LED3") (pin "1") (pinfunction "1_1") (pintype "passive"))
      (node (ref "U3") (pin "6") (pinfunction "OUT_6") (pintype "output"))
      (node (ref "VO1") (pin "TP") (pinfunction "TP_TP") (pintype "input"))
    )
    (net (code "91") (name "Net-(U3-P3)") (class "Default")
      (node (ref "J5") (pin "1") (pinfunction "1_1") (pintype "bidirectional"))
      (node (ref "U3") (pin "2") (pinfunction "P3_2") (pintype "input"))
    )
    (net (code "92") (name "Net-(U3-REF)") (class "Default")
      (node (ref "J5") (pin "3") (pinfunction "3_3") (pintype "bidirectional"))
      (node (ref "U3") (pin "5") (pinfunction "REF_5") (pintype "input"))
    )
    (net (code "93") (name "Net-(U4-P0A)") (class "Default")
      (node (ref "LED4") (pin "2") (pinfunction "2_2") (pintype "passive"))
      (node (ref "U4") (pin "13") (pinfunction "P0A_13") (pintype "bidirectional"))
    )
    (net (code "94") (name "Net-(U5-P0A)") (class "Default")
      (node (ref "LED3") (pin "2") (pinfunction "2_2") (pintype "passive"))
      (node (ref "U5") (pin "13") (pinfunction "P0A_13") (pintype "bidirectional"))
    )
    (net (code "95") (name "Net-(U6-GATE)") (class "Default")
      (node (ref "U6") (pin "5") (pinfunction "GATE_5") (pintype "passive"))
      (node (ref "U7") (pin "1") (pinfunction "G_1") (pintype "passive"))
    )
    (net (code "96") (name "OC1") (class "Default")
      (node (ref "IC1") (pin "46") (pinfunction "OC1/RD0_46") (pintype "bidirectional"))
      (node (ref "IC4") (pin "2") (pinfunction "VF1-_2") (pintype "bidirectional"))
      (node (ref "OC1") (pin "TP") (pinfunction "TP_TP") (pintype "input"))
    )
    (net (code "97") (name "OC2") (class "Default")
      (node (ref "IC1") (pin "49") (pinfunction "OC2/RD1_49") (pintype "bidirectional"))
      (node (ref "IC4") (pin "3") (pinfunction "VF2-_3") (pintype "bidirectional"))
      (node (ref "OC2") (pin "TP") (pinfunction "TP_TP") (pintype "input"))
    )
    (net (code "98") (name "OC3") (class "Default")
      (node (ref "IC1") (pin "50") (pinfunction "OC3/RD2_50") (pintype "bidirectional"))
      (node (ref "IC3") (pin "2") (pinfunction "VF1-_2") (pintype "bidirectional"))
      (node (ref "OC3") (pin "TP") (pinfunction "TP_TP") (pintype "input"))
    )
    (net (code "99") (name "OC4") (class "Default")
      (node (ref "IC1") (pin "51") (pinfunction "OC4/RD3_51") (pintype "bidirectional"))
      (node (ref "IC3") (pin "3") (pinfunction "VF2-_3") (pintype "bidirectional"))
      (node (ref "OC4") (pin "TP") (pinfunction "TP_TP") (pintype "input"))
    )
    (net (code "100") (name "PGC_2") (class "Default")
      (node (ref "IC1") (pin "48") (pinfunction "PGEC2/SOSCO/T1CK/CN0/RC14_48") (pintype "bidirectional"))
      (node (ref "J1") (pin "5") (pinfunction "S_5") (pintype "passive"))
    )
    (net (code "101") (name "PGD_2") (class "Default")
      (node (ref "IC1") (pin "47") (pinfunction "PGED2/SOSCI/T4CK/CN1/RC13_47") (pintype "bidirectional"))
      (node (ref "J1") (pin "4") (pinfunction "S_4") (pintype "passive"))
    )
    (net (code "102") (name "PWM2") (class "Default")
      (node (ref "JP4") (pin "3") (pinfunction "3_3") (pintype "passive"))
    )
    (net (code "103") (name "PWM3") (class "Default")
      (node (ref "JP4") (pin "4") (pinfunction "4_4") (pintype "passive"))
    )
    (net (code "104") (name "PWM5") (class "Default")
      (node (ref "JP4") (pin "6") (pinfunction "6_6") (pintype "passive"))
    )
    (net (code "105") (name "PWM6") (class "Default")
      (node (ref "JP4") (pin "7") (pinfunction "7_7") (pintype "passive"))
    )
    (net (code "106") (name "PWM7") (class "Default")
      (node (ref "JP4") (pin "8") (pinfunction "8_8") (pintype "passive"))
    )
    (net (code "107") (name "PWM8") (class "Default")
      (node (ref "JP3") (pin "1") (pinfunction "1_1") (pintype "passive"))
    )
    (net (code "108") (name "PWM11") (class "Default")
      (node (ref "JP3") (pin "4") (pinfunction "4_4") (pintype "passive"))
    )
    (net (code "109") (name "PWM12") (class "Default")
      (node (ref "JP3") (pin "5") (pinfunction "5_5") (pintype "passive"))
    )
    (net (code "110") (name "PWM13") (class "Default")
      (node (ref "JP3") (pin "6") (pinfunction "6_6") (pintype "passive"))
    )
    (net (code "111") (name "RESET~{}") (class "Default")
      (node (ref "IC1") (pin "7") (pinfunction "~{MCLR}_7") (pintype "bidirectional"))
      (node (ref "J1") (pin "1") (pinfunction "S_1") (pintype "passive"))
      (node (ref "R2") (pin "2") (pinfunction "2_2") (pintype "passive"))
    )
    (net (code "112") (name "RX") (class "Default")
      (node (ref "JP4") (pin "1") (pinfunction "1_1") (pintype "passive"))
    )
    (net (code "113") (name "RXD0") (class "Default")
      (node (ref "JP5") (pin "2") (pinfunction "2_2") (pintype "passive"))
    )
    (net (code "114") (name "RXD1") (class "Default")
      (node (ref "JP5") (pin "4") (pinfunction "4_4") (pintype "passive"))
    )
    (net (code "115") (name "RXD2") (class "Default")
      (node (ref "JP5") (pin "6") (pinfunction "6_6") (pintype "passive"))
    )
    (net (code "116") (name "RX_1") (class "Default")
      (node (ref "IC1") (pin "34") (pinfunction "U1RX/SDI1/RF2_34") (pintype "bidirectional"))
      (node (ref "IC2") (pin "1") (pinfunction "TXD_1") (pintype "output"))
    )
    (net (code "117") (name "SCK2") (class "Default")
      (node (ref "IC1") (pin "4") (pinfunction "SCK2/CN8/RG6_4") (pintype "bidirectional"))
      (node (ref "SCK") (pin "TP") (pinfunction "TP_TP") (pintype "input"))
      (node (ref "U4") (pin "2") (pinfunction "SCK_2") (pintype "input"))
      (node (ref "U5") (pin "2") (pinfunction "SCK_2") (pintype "input"))
    )
    (net (code "118") (name "SCL0-3") (class "Default")
      (node (ref "JP5") (pin "8") (pinfunction "8_8") (pintype "passive"))
    )
    (net (code "119") (name "SCL1") (class "Default")
      (node (ref "IC1") (pin "37") (pinfunction "SCL1/RG2_37") (pintype "bidirectional"))
      (node (ref "JP3") (pin "10") (pinfunction "10_10") (pintype "passive"))
      (node (ref "R4") (pin "2") (pinfunction "2_2") (pintype "passive"))
    )
    (net (code "120") (name "SDA0-3") (class "Default")
      (node (ref "JP5") (pin "7") (pinfunction "7_7") (pintype "passive"))
    )
    (net (code "121") (name "SDA1") (class "Default")
      (node (ref "IC1") (pin "36") (pinfunction "SDA1/RG3_36") (pintype "bidirectional"))
      (node (ref "JP3") (pin "9") (pinfunction "9_9") (pintype "passive"))
      (node (ref "R3") (pin "2") (pinfunction "2_2") (pintype "passive"))
    )
    (net (code "122") (name "SDI2") (class "Default")
      (node (ref "IC1") (pin "5") (pinfunction "SDI2/CN9/RG7_5") (pintype "bidirectional"))
      (node (ref "SDI") (pin "TP") (pinfunction "TP_TP") (pintype "input"))
      (node (ref "U4") (pin "5") (pinfunction "SDO_5") (pintype "output"))
      (node (ref "U5") (pin "5") (pinfunction "SDO_5") (pintype "output"))
    )
    (net (code "123") (name "SDO2") (class "Default")
      (node (ref "IC1") (pin "6") (pinfunction "SDO2/CN10/RG8_6") (pintype "bidirectional"))
      (node (ref "SDO") (pin "TP") (pinfunction "TP_TP") (pintype "input"))
      (node (ref "U4") (pin "4") (pinfunction "SDI_4") (pintype "input"))
      (node (ref "U5") (pin "4") (pinfunction "SDI_4") (pintype "input"))
    )
    (net (code "124") (name "SS1{slash}PWM4") (class "Default")
      (node (ref "JP4") (pin "5") (pinfunction "5_5") (pintype "passive"))
    )
    (net (code "125") (name "SUPPLY_STATUS") (class "Default")
      (node (ref "IC1") (pin "45") (pinfunction "IC4/INT4/RD11_45") (pintype "bidirectional"))
      (node (ref "R33") (pin "2") (pinfunction "2_2") (pintype "passive"))
      (node (ref "U6") (pin "4") (pinfunction "STAT_4") (pintype "output"))
    )
    (net (code "126") (name "TX") (class "Default")
      (node (ref "JP4") (pin "2") (pinfunction "2_2") (pintype "passive"))
    )
    (net (code "127") (name "TXD0") (class "Default")
      (node (ref "JP5") (pin "1") (pinfunction "1_1") (pintype "passive"))
    )
    (net (code "128") (name "TXD1") (class "Default")
      (node (ref "JP5") (pin "3") (pinfunction "3_3") (pintype "passive"))
    )
    (net (code "129") (name "TXD2") (class "Default")
      (node (ref "JP5") (pin "5") (pinfunction "5_5") (pintype "passive"))
    )
    (net (code "130") (name "TX_1") (class "Default")
      (node (ref "IC1") (pin "33") (pinfunction "U1TX/SDO1/RF3_33") (pintype "bidirectional"))
      (node (ref "IC2") (pin "5") (pinfunction "RXD_5") (pintype "input"))
    )
    (net (code "131") (name "USB_5V") (class "Default")
      (node (ref "C6") (pin "1") (pinfunction "1_1") (pintype "passive"))
      (node (ref "D4") (pin "2") (pinfunction "A_2") (pintype "bidirectional"))
      (node (ref "F1") (pin "1") (pinfunction "1_1") (pintype "passive"))
      (node (ref "IC2") (pin "20") (pinfunction "VCC_20") (pintype "power_in"))
      (node (ref "R5") (pin "2") (pinfunction "2_2") (pintype "passive"))
      (node (ref "R6") (pin "2") (pinfunction "2_2") (pintype "passive"))
      (node (ref "R7") (pin "2") (pinfunction "2_2") (pintype "passive"))
    )
    (net (code "132") (name "VCC") (class "Default")
      (node (ref "+HV") (pin "TP") (pinfunction "TP_TP") (pintype "input"))
      (node (ref "C32") (pin "1") (pinfunction "1_1") (pintype "passive"))
      (node (ref "C35") (pin "1") (pinfunction "1_1") (pintype "passive"))
      (node (ref "C37") (pin "1") (pinfunction "1_1") (pintype "passive"))
      (node (ref "PS2") (pin "5") (pinfunction "+VOUT_5") (pintype "bidirectional"))
      (node (ref "Q2") (pin "2") (pinfunction "C_2") (pintype "bidirectional"))
      (node (ref "Q4") (pin "2") (pinfunction "C_2") (pintype "bidirectional"))
      (node (ref "R14") (pin "2") (pinfunction "2_2") (pintype "passive"))
      (node (ref "R21") (pin "2") (pinfunction "2_2") (pintype "passive"))
    )
    (net (code "133") (name "VIN") (class "Default")
      (node (ref "C26") (pin "1") (pinfunction "1_1") (pintype "passive"))
      (node (ref "D2") (pin "P$1") (pinfunction "K_P$1") (pintype "bidirectional"))
      (node (ref "D3") (pin "K") (pinfunction "C_K") (pintype "passive"))
      (node (ref "IC14") (pin "1") (pinfunction "EN_1") (pintype "bidirectional"))
      (node (ref "IC14") (pin "2") (pinfunction "IN_2") (pintype "bidirectional"))
      (node (ref "JP6") (pin "8") (pinfunction "8_8") (pintype "passive"))
    )
    (net (code "134") (name "VIN+") (class "Default")
      (node (ref "J7") (pin "1") (pinfunction "1_1") (pintype "bidirectional"))
      (node (ref "L1") (pin "2") (pinfunction "2_2") (pintype "passive"))
    )
    (net (code "135") (name "VIN_5V") (class "Default")
      (node (ref "C25") (pin "1") (pinfunction "1_1") (pintype "passive"))
      (node (ref "C29") (pin "+") (pinfunction "+_+") (pintype "passive"))
      (node (ref "C30") (pin "1") (pinfunction "+_1") (pintype "bidirectional"))
      (node (ref "D4") (pin "1") (pinfunction "K_1") (pintype "bidirectional"))
      (node (ref "D5") (pin "1") (pinfunction "K_1") (pintype "bidirectional"))
      (node (ref "IC13") (pin "1") (pinfunction "IN_1") (pintype "bidirectional"))
      (node (ref "IC13") (pin "3") (pinfunction "EN_3") (pintype "bidirectional"))
      (node (ref "R33") (pin "1") (pinfunction "1_1") (pintype "passive"))
      (node (ref "S3") (pin "3") (pinfunction "3_3") (pintype "bidirectional"))
      (node (ref "U6") (pin "6") (pinfunction "SENSE_6") (pintype "input"))
      (node (ref "U7") (pin "2") (pinfunction "S_2") (pintype "passive"))
      (node (ref "U8") (pin "1") (pinfunction "VIN_1") (pintype "input"))
      (node (ref "VIN5V") (pin "TP") (pinfunction "TP_TP") (pintype "input"))
    )
    (net (code "136") (name "VSS") (class "Default")
      (node (ref "-HV") (pin "TP") (pinfunction "TP_TP") (pintype "input"))
      (node (ref "C31") (pin "2") (pinfunction "2_2") (pintype "passive"))
      (node (ref "C36") (pin "1") (pinfunction "1_1") (pintype "passive"))
      (node (ref "C38") (pin "1") (pinfunction "1_1") (pintype "passive"))
      (node (ref "PS1") (pin "8") (pinfunction "-VOUT3_8") (pintype "bidirectional"))
      (node (ref "Q1") (pin "2") (pinfunction "C_2") (pintype "bidirectional"))
      (node (ref "Q3") (pin "2") (pinfunction "C_2") (pintype "bidirectional"))
      (node (ref "R11") (pin "1") (pinfunction "1_1") (pintype "passive"))
      (node (ref "R18") (pin "1") (pinfunction "1_1") (pintype "passive"))
    )
    (net (code "137") (name "VSTIM1") (class "Default")
      (node (ref "IC5") (pin "3") (pinfunction "+IN_3") (pintype "input"))
      (node (ref "U1") (pin "1") (pinfunction "OUT1_1") (pintype "passive"))
      (node (ref "U1") (pin "2") (pinfunction "IN1-_2") (pintype "passive"))
      (node (ref "VSTIM1") (pin "TP") (pinfunction "TP_TP") (pintype "input"))
    )
    (net (code "138") (name "VSTIM2") (class "Default")
      (node (ref "IC8") (pin "3") (pinfunction "+IN_3") (pintype "input"))
      (node (ref "U1") (pin "6") (pinfunction "IN2-_6") (pintype "passive"))
      (node (ref "U1") (pin "7") (pinfunction "OUT2_7") (pintype "passive"))
      (node (ref "VSTIM2") (pin "TP") (pinfunction "TP_TP") (pintype "input"))
    )
    (net (code "139") (name "XVCC") (class "Default")
      (node (ref "F1") (pin "2") (pinfunction "2_2") (pintype "passive"))
      (node (ref "J2") (pin "1") (pinfunction "VBUS_1") (pintype "bidirectional"))
      (node (ref "TP3") (pin "X") (pinfunction "P$1_X") (pintype "passive"))
    )
    (net (code "140") (name "unconnected-(IC1-AN3{slash}CN5{slash}RB3-Pad13)") (class "Default")
      (node (ref "IC1") (pin "13") (pinfunction "AN3/CN5/RB3_13") (pintype "bidirectional"))
    )
    (net (code "141") (name "unconnected-(IC1-AN4{slash}IC7{slash}CN6{slash}RB4-Pad12)") (class "Default")
      (node (ref "IC1") (pin "12") (pinfunction "AN4/IC7/CN6/RB4_12") (pintype "bidirectional"))
    )
    (net (code "142") (name "unconnected-(IC1-AN5{slash}IC8{slash}CN7{slash}RB5-Pad11)") (class "Default")
      (node (ref "IC1") (pin "11") (pinfunction "AN5/IC8/CN7/RB5_11") (pintype "bidirectional"))
    )
    (net (code "143") (name "unconnected-(IC1-AN15{slash}OCFB{slash}CN12{slash}RB15-Pad30)") (class "Default")
      (node (ref "IC1") (pin "30") (pinfunction "AN15/OCFB/CN12/RB15_30") (pintype "bidirectional"))
    )
    (net (code "144") (name "unconnected-(IC1-AN16{slash}T2CK{slash}T7CK{slash}RC1-Pad2)") (class "Default")
      (node (ref "IC1") (pin "2") (pinfunction "AN16/T2CK/T7CK/RC1_2") (pintype "bidirectional"))
    )
    (net (code "145") (name "unconnected-(IC1-AN17{slash}T3CK{slash}T6CK{slash}RC2-Pad3)") (class "Default")
      (node (ref "IC1") (pin "3") (pinfunction "AN17/T3CK/T6CK/RC2_3") (pintype "bidirectional"))
    )
    (net (code "146") (name "unconnected-(IC1-C1RX{slash}RF0-Pad58)") (class "Default")
      (node (ref "IC1") (pin "58") (pinfunction "C1RX/RF0_58") (pintype "bidirectional"))
    )
    (net (code "147") (name "unconnected-(IC1-C1TX{slash}RF1-Pad59)") (class "Default")
      (node (ref "IC1") (pin "59") (pinfunction "C1TX/RF1_59") (pintype "bidirectional"))
    )
    (net (code "148") (name "unconnected-(IC1-COFS{slash}RG15-Pad1)") (class "Default")
      (node (ref "IC1") (pin "1") (pinfunction "COFS/RG15_1") (pintype "bidirectional"))
    )
    (net (code "149") (name "unconnected-(IC1-CSCK{slash}RG14-Pad62)") (class "Default")
      (node (ref "IC1") (pin "62") (pinfunction "CSCK/RG14_62") (pintype "bidirectional"))
    )
    (net (code "150") (name "unconnected-(IC1-CSDI{slash}RG12-Pad63)") (class "Default")
      (node (ref "IC1") (pin "63") (pinfunction "CSDI/RG12_63") (pintype "bidirectional"))
    )
    (net (code "151") (name "unconnected-(IC1-CSDO{slash}RG13-Pad64)") (class "Default")
      (node (ref "IC1") (pin "64") (pinfunction "CSDO/RG13_64") (pintype "bidirectional"))
    )
    (net (code "152") (name "unconnected-(IC1-OC5{slash}IC5{slash}CN13{slash}RD4-Pad52)") (class "Default")
      (node (ref "IC1") (pin "52") (pinfunction "OC5/IC5/CN13/RD4_52") (pintype "bidirectional"))
    )
    (net (code "153") (name "unconnected-(IC1-OC6{slash}IC6{slash}CN14{slash}RD5-Pad53)") (class "Default")
      (node (ref "IC1") (pin "53") (pinfunction "OC6/IC6/CN14/RD5_53") (pintype "bidirectional"))
    )
    (net (code "154") (name "unconnected-(IC1-OC7{slash}CN15{slash}RD6-Pad54)") (class "Default")
      (node (ref "IC1") (pin "54") (pinfunction "OC7/CN15/RD6_54") (pintype "bidirectional"))
    )
    (net (code "155") (name "unconnected-(IC1-OC8{slash}CN16{slash}RD7-Pad55)") (class "Default")
      (node (ref "IC1") (pin "55") (pinfunction "OC8/CN16/RD7_55") (pintype "bidirectional"))
    )
    (net (code "156") (name "unconnected-(IC1-OSC1{slash}CLKIN{slash}RC12-Pad39)") (class "Default")
      (node (ref "IC1") (pin "39") (pinfunction "OSC1/CLKIN/RC12_39") (pintype "bidirectional"))
    )
    (net (code "157") (name "unconnected-(IC1-OSC2{slash}CLKO{slash}RC15-Pad40)") (class "Default")
      (node (ref "IC1") (pin "40") (pinfunction "OSC2/CLKO/RC15_40") (pintype "bidirectional"))
    )
    (net (code "158") (name "unconnected-(IC1-PGEC1{slash}AN6{slash}OCFA{slash}RB6-Pad17)") (class "Default")
      (node (ref "IC1") (pin "17") (pinfunction "PGEC1/AN6/OCFA/RB6_17") (pintype "bidirectional"))
    )
    (net (code "159") (name "unconnected-(IC1-RG0-Pad61)") (class "Default")
      (node (ref "IC1") (pin "61") (pinfunction "RG0_61") (pintype "bidirectional"))
    )
    (net (code "160") (name "unconnected-(IC1-RG1-Pad60)") (class "Default")
      (node (ref "IC1") (pin "60") (pinfunction "RG1_60") (pintype "bidirectional"))
    )
    (net (code "161") (name "unconnected-(IC1-TCK{slash}AN12{slash}RB12-Pad27)") (class "Default")
      (node (ref "IC1") (pin "27") (pinfunction "TCK/AN12/RB12_27") (pintype "bidirectional"))
    )
    (net (code "162") (name "unconnected-(IC1-TDI{slash}AN13{slash}RB13-Pad28)") (class "Default")
      (node (ref "IC1") (pin "28") (pinfunction "TDI/AN13/RB13_28") (pintype "bidirectional"))
    )
    (net (code "163") (name "unconnected-(IC1-TDO{slash}AN11{slash}RB11-Pad24)") (class "Default")
      (node (ref "IC1") (pin "24") (pinfunction "TDO/AN11/RB11_24") (pintype "bidirectional"))
    )
    (net (code "164") (name "unconnected-(IC1-TMS{slash}AN10{slash}RB10-Pad23)") (class "Default")
      (node (ref "IC1") (pin "23") (pinfunction "TMS/AN10/RB10_23") (pintype "bidirectional"))
    )
    (net (code "165") (name "unconnected-(IC1-U2RX{slash}SDA2{slash}CN17{slash}RF4-Pad31)") (class "Default")
      (node (ref "IC1") (pin "31") (pinfunction "U2RX/SDA2/CN17/RF4_31") (pintype "bidirectional"))
    )
    (net (code "166") (name "unconnected-(IC1-U2TX{slash}SCL2{slash}CN18{slash}RF5-Pad32)") (class "Default")
      (node (ref "IC1") (pin "32") (pinfunction "U2TX/SCL2/CN18/RF5_32") (pintype "bidirectional"))
    )
    (net (code "167") (name "unconnected-(IC1-~{U2CTS}{slash}AN8{slash}RB8-Pad21)") (class "Default")
      (node (ref "IC1") (pin "21") (pinfunction "~{U2CTS}/AN8/RB8_21") (pintype "bidirectional"))
    )
    (net (code "168") (name "unconnected-(IC1-~{U2RTS}{slash}AN14{slash}RB14-Pad29)") (class "Default")
      (node (ref "IC1") (pin "29") (pinfunction "~{U2RTS}/AN14/RB14_29") (pintype "bidirectional"))
    )
    (net (code "169") (name "unconnected-(IC2-CBUS2-Pad13)") (class "Default")
      (node (ref "IC2") (pin "13") (pinfunction "CBUS2_13") (pintype "bidirectional"))
    )
    (net (code "170") (name "unconnected-(IC2-CBUS4-Pad12)") (class "Default")
      (node (ref "IC2") (pin "12") (pinfunction "CBUS4_12") (pintype "bidirectional"))
    )
    (net (code "171") (name "unconnected-(IC2-OSCI-Pad27)") (class "Default")
      (node (ref "IC2") (pin "27") (pinfunction "OSCI_27") (pintype "input"))
    )
    (net (code "172") (name "unconnected-(IC2-OSCO-Pad28)") (class "Default")
      (node (ref "IC2") (pin "28") (pinfunction "OSCO_28") (pintype "output"))
    )
    (net (code "173") (name "unconnected-(IC2-~{CTS}-Pad11)") (class "Default")
      (node (ref "IC2") (pin "11") (pinfunction "~{CTS}_11") (pintype "input"))
    )
    (net (code "174") (name "unconnected-(IC2-~{DCD}-Pad10)") (class "Default")
      (node (ref "IC2") (pin "10") (pinfunction "~{DCD}_10") (pintype "input"))
    )
    (net (code "175") (name "unconnected-(IC2-~{DSR}-Pad9)") (class "Default")
      (node (ref "IC2") (pin "9") (pinfunction "~{DSR}_9") (pintype "input"))
    )
    (net (code "176") (name "unconnected-(IC2-~{DTR}-Pad2)") (class "Default")
      (node (ref "IC2") (pin "2") (pinfunction "~{DTR}_2") (pintype "output"))
    )
    (net (code "177") (name "unconnected-(IC2-~{RESET}-Pad19)") (class "Default")
      (node (ref "IC2") (pin "19") (pinfunction "~{RESET}_19") (pintype "input"))
    )
    (net (code "178") (name "unconnected-(IC2-~{RI}-Pad6)") (class "Default")
      (node (ref "IC2") (pin "6") (pinfunction "~{RI}_6") (pintype "input"))
    )
    (net (code "179") (name "unconnected-(IC2-~{RTS}-Pad3)") (class "Default")
      (node (ref "IC2") (pin "3") (pinfunction "~{RTS}_3") (pintype "output"))
    )
    (net (code "180") (name "unconnected-(IC5-NC-Pad8)") (class "Default")
      (node (ref "IC5") (pin "8") (pinfunction "NC_8") (pintype "no_connect"))
    )
    (net (code "181") (name "unconnected-(IC7-NC-Pad1)") (class "Default")
      (node (ref "IC7") (pin "1") (pinfunction "NC_1") (pintype "no_connect"))
    )
    (net (code "182") (name "unconnected-(IC7-NC_1-Pad5)") (class "Default")
      (node (ref "IC7") (pin "5") (pinfunction "NC_1_5") (pintype "bidirectional"))
    )
    (net (code "183") (name "unconnected-(IC7-NC_2-Pad8)") (class "Default")
      (node (ref "IC7") (pin "8") (pinfunction "NC_2_8") (pintype "bidirectional"))
    )
    (net (code "184") (name "unconnected-(IC8-NC-Pad8)") (class "Default")
      (node (ref "IC8") (pin "8") (pinfunction "NC_8") (pintype "no_connect"))
    )
    (net (code "185") (name "unconnected-(IC10-NC-Pad1)") (class "Default")
      (node (ref "IC10") (pin "1") (pinfunction "NC_1") (pintype "no_connect"))
    )
    (net (code "186") (name "unconnected-(IC10-NC_1-Pad5)") (class "Default")
      (node (ref "IC10") (pin "5") (pinfunction "NC_1_5") (pintype "bidirectional"))
    )
    (net (code "187") (name "unconnected-(IC10-NC_2-Pad8)") (class "Default")
      (node (ref "IC10") (pin "8") (pinfunction "NC_2_8") (pintype "bidirectional"))
    )
    (net (code "188") (name "unconnected-(J2-ID-Pad4)") (class "Default")
      (node (ref "J2") (pin "4") (pinfunction "ID_4") (pintype "bidirectional"))
    )
    (net (code "189") (name "unconnected-(J3-Pad3)") (class "Default")
      (node (ref "J3") (pin "3") (pinfunction "3_3") (pintype "passive"))
    )
    (net (code "190") (name "unconnected-(J4-Pad3)") (class "Default")
      (node (ref "J4") (pin "3") (pinfunction "3_3") (pintype "passive"))
    )
    (net (code "191") (name "unconnected-(JP6-Pad1)") (class "Default")
      (node (ref "JP6") (pin "1") (pinfunction "1_1") (pintype "passive"))
    )
    (net (code "192") (name "unconnected-(JP6-Pad2)") (class "Default")
      (node (ref "JP6") (pin "2") (pinfunction "2_2") (pintype "passive"))
    )
    (net (code "193") (name "unconnected-(JP6-Pad4)") (class "Default")
      (node (ref "JP6") (pin "4") (pinfunction "4_4") (pintype "passive"))
    )
    (net (code "194") (name "unconnected-(JP7-Pad2)") (class "Default")
      (node (ref "JP7") (pin "2") (pinfunction "2_2") (pintype "passive"))
    )
    (net (code "195") (name "unconnected-(JP7-Pad3)") (class "Default")
      (node (ref "JP7") (pin "3") (pinfunction "3_3") (pintype "passive"))
    )
    (net (code "196") (name "unconnected-(PS1--VOUT1-Pad6)") (class "Default")
      (node (ref "PS1") (pin "6") (pinfunction "-VOUT1_6") (pintype "bidirectional"))
    )
    (net (code "197") (name "unconnected-(PS1--VOUT2-Pad7)") (class "Default")
      (node (ref "PS1") (pin "7") (pinfunction "-VOUT2_7") (pintype "bidirectional"))
    )
    (net (code "198") (name "unconnected-(PS2--VOUT1-Pad6)") (class "Default")
      (node (ref "PS2") (pin "6") (pinfunction "-VOUT1_6") (pintype "bidirectional"))
    )
    (net (code "199") (name "unconnected-(PS2--VOUT2-Pad7)") (class "Default")
      (node (ref "PS2") (pin "7") (pinfunction "-VOUT2_7") (pintype "bidirectional"))
    )
    (net (code "200") (name "unconnected-(U2-M3-Pad9)") (class "Default")
      (node (ref "U2") (pin "9") (pinfunction "M3_9") (pintype "input"))
    )
    (net (code "201") (name "unconnected-(U2-M9-Pad8)") (class "Default")
      (node (ref "U2") (pin "8") (pinfunction "M9_8") (pintype "input"))
    )
    (net (code "202") (name "unconnected-(U2-P9-Pad3)") (class "Default")
      (node (ref "U2") (pin "3") (pinfunction "P9_3") (pintype "input"))
    )
    (net (code "203") (name "unconnected-(U3-M3-Pad9)") (class "Default")
      (node (ref "U3") (pin "9") (pinfunction "M3_9") (pintype "input"))
    )
    (net (code "204") (name "unconnected-(U3-M9-Pad8)") (class "Default")
      (node (ref "U3") (pin "8") (pinfunction "M9_8") (pintype "input"))
    )
    (net (code "205") (name "unconnected-(U3-P9-Pad3)") (class "Default")
      (node (ref "U3") (pin "3") (pinfunction "P9_3") (pintype "input"))
    )
    (net (code "206") (name "unconnected-(U4-NC-Pad8)") (class "Default")
      (node (ref "U4") (pin "8") (pinfunction "NC_8") (pintype "no_connect"))
    )
    (net (code "207") (name "unconnected-(U5-NC-Pad8)") (class "Default")
      (node (ref "U5") (pin "8") (pinfunction "NC_8") (pintype "no_connect"))
    )
  )
)
